# electrosteel2020_10_arrange6_synthboards.net
KiCad netlist of a schematic drawn in EAGLE
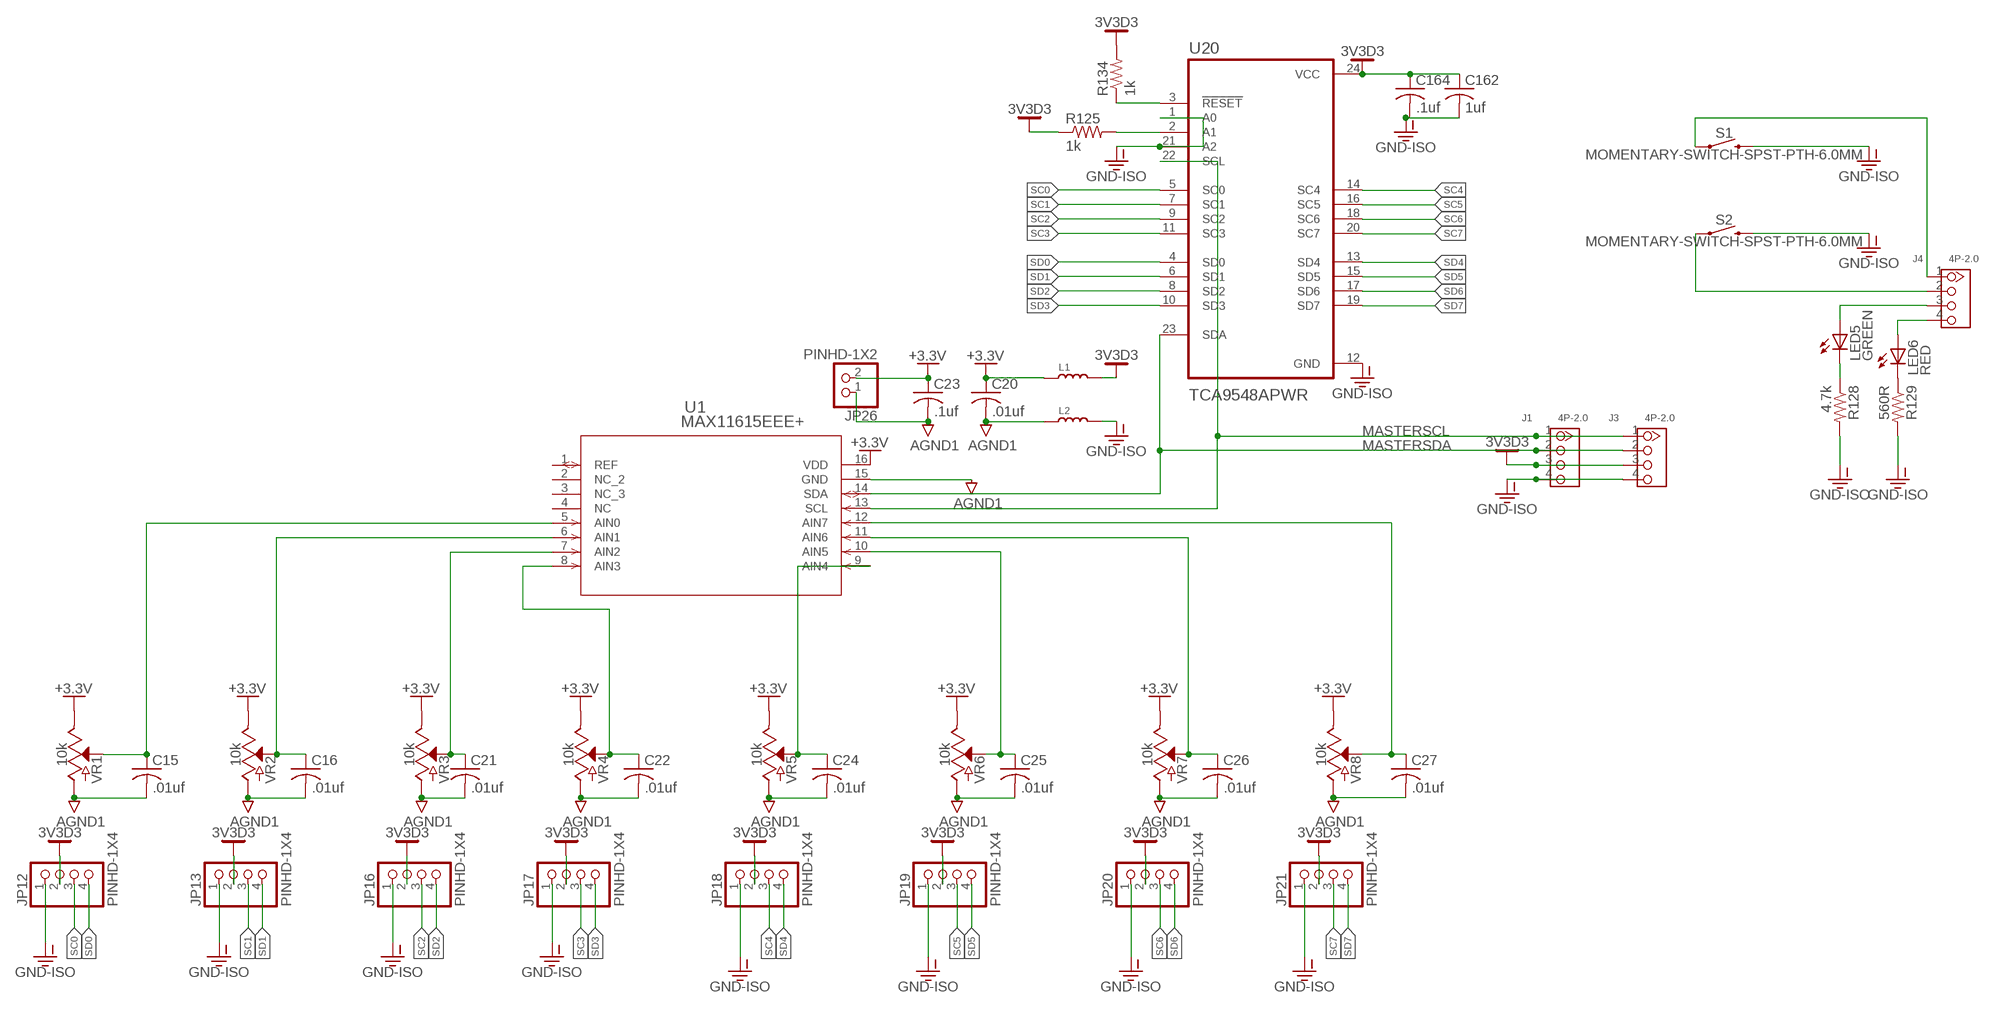
[diagram p0: schematic, sheet 1, part 1 of 2]
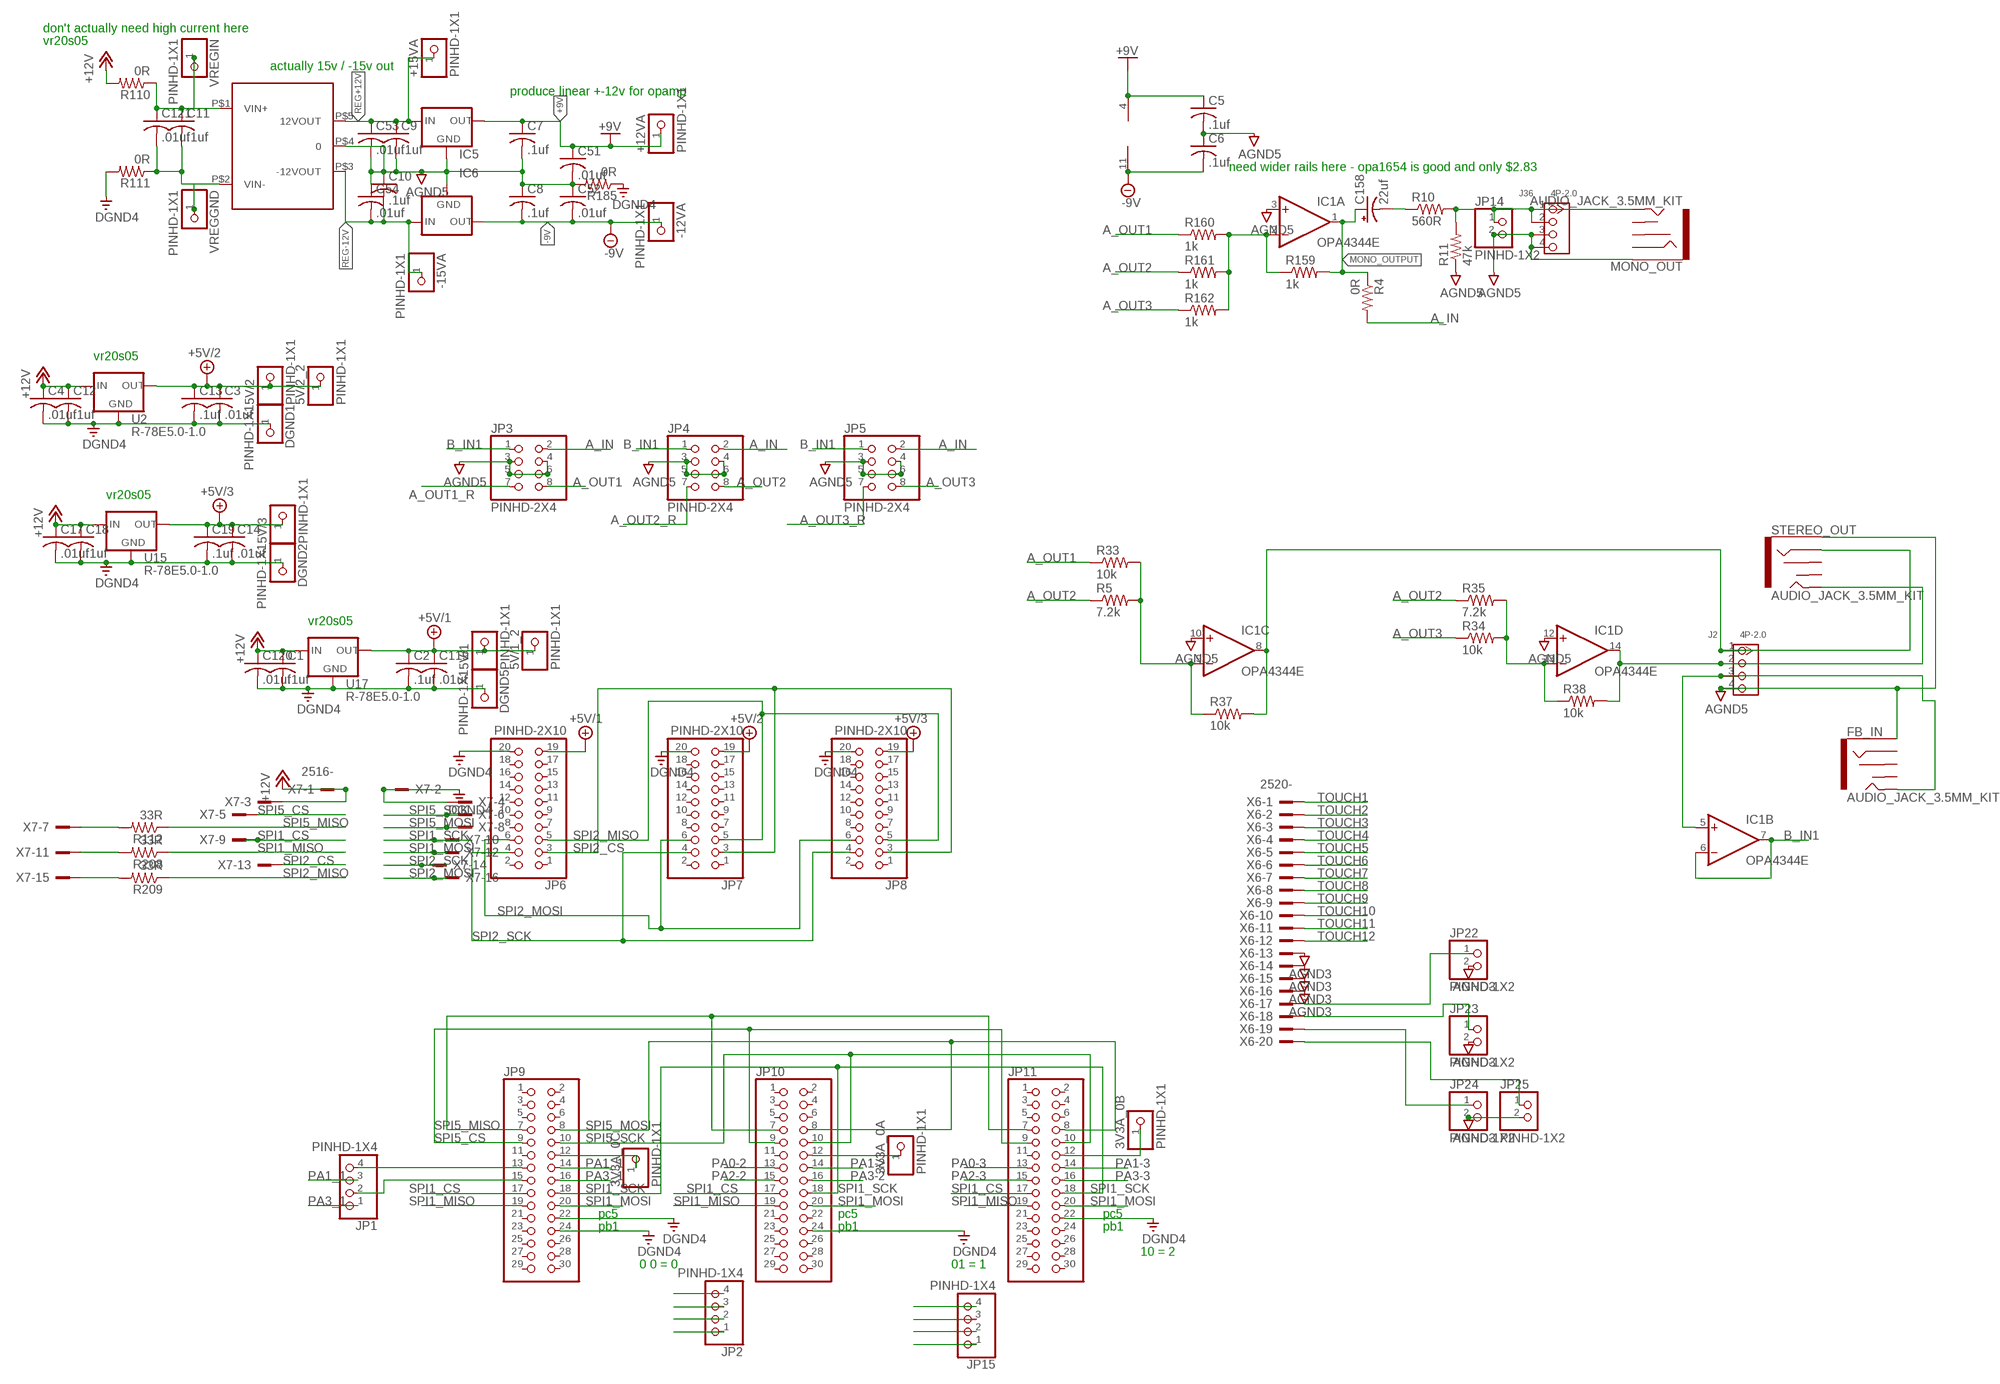
[diagram p1: schematic, sheet 1, part 2 of 2]

(export (version "E")
  (design (tool "Eeschema 10.0.6"))
  (components
    (comp (ref "+12VA")
      (value "PINHD-1X1")
      (footprint "eagle-import:1X01")
      (fields (field (name "PARTNO") "*DNP"))
      (libsource (lib "eagle-import") (part "PINHD-1X1"))
    )
    (comp (ref "+15VA")
      (value "PINHD-1X1")
      (footprint "eagle-import:1X01")
      (fields (field (name "PARTNO") "*DNP"))
      (libsource (lib "eagle-import") (part "PINHD-1X1"))
    )
    (comp (ref "-12VA")
      (value "PINHD-1X1")
      (footprint "eagle-import:1X01")
      (fields (field (name "PARTNO") "*DNP"))
      (libsource (lib "eagle-import") (part "PINHD-1X1"))
    )
    (comp (ref "-15VA")
      (value "PINHD-1X1")
      (footprint "eagle-import:1X01")
      (fields (field (name "PARTNO") "*DNP"))
      (libsource (lib "eagle-import") (part "PINHD-1X1"))
    )
    (comp (ref "3V3A_0A")
      (value "PINHD-1X1")
      (footprint "eagle-import:1X01")
      (fields (field (name "PARTNO") "*DNP"))
      (libsource (lib "eagle-import") (part "PINHD-1X1"))
    )
    (comp (ref "3V3A_0B")
      (value "PINHD-1X1")
      (footprint "eagle-import:1X01")
      (fields (field (name "PARTNO") "*DNP"))
      (libsource (lib "eagle-import") (part "PINHD-1X1"))
    )
    (comp (ref "3V3A_0C")
      (value "PINHD-1X1")
      (footprint "eagle-import:1X01")
      (fields (field (name "PARTNO") "*DNP"))
      (libsource (lib "eagle-import") (part "PINHD-1X1"))
    )
    (comp (ref "5V/1")
      (value "PINHD-1X1")
      (footprint "eagle-import:1X01")
      (fields (field (name "PARTNO") "*DNP"))
      (libsource (lib "eagle-import") (part "PINHD-1X1"))
    )
    (comp (ref "5V/1_2")
      (value "PINHD-1X1")
      (footprint "eagle-import:1X01")
      (fields (field (name "PARTNO") "*DNP"))
      (libsource (lib "eagle-import") (part "PINHD-1X1"))
    )
    (comp (ref "5V/2")
      (value "PINHD-1X1")
      (footprint "eagle-import:1X01")
      (fields (field (name "PARTNO") "*DNP"))
      (libsource (lib "eagle-import") (part "PINHD-1X1"))
    )
    (comp (ref "5V/2_2")
      (value "PINHD-1X1")
      (footprint "eagle-import:1X01")
      (fields (field (name "PARTNO") "*DNP"))
      (libsource (lib "eagle-import") (part "PINHD-1X1"))
    )
    (comp (ref "5V/3")
      (value "PINHD-1X1")
      (footprint "eagle-import:1X01")
      (fields (field (name "PARTNO") "*DNP"))
      (libsource (lib "eagle-import") (part "PINHD-1X1"))
    )
    (comp (ref "C1")
      (value ".1uf")
      (footprint "eagle-import:C0603")
      (fields (field (name "PARTNO") "TMK063B7103KP-F"))
      (libsource (lib "eagle-import") (part "rcl_334_C-USC0603"))
    )
    (comp (ref "C2")
      (value ".1uf")
      (footprint "eagle-import:C0603")
      (fields (field (name "PARTNO") "TMK063B7103KP-F"))
      (libsource (lib "eagle-import") (part "rcl_334_C-USC0603"))
    )
    (comp (ref "C3")
      (value ".01uf")
      (footprint "eagle-import:C0603")
      (fields (field (name "PARTNO") "TMK063B7103KP-F"))
      (libsource (lib "eagle-import") (part "rcl_334_C-USC0603"))
    )
    (comp (ref "C4")
      (value ".01uf")
      (footprint "eagle-import:C0603")
      (fields (field (name "PARTNO") "TMK063B7103KP-F"))
      (libsource (lib "eagle-import") (part "rcl_334_C-USC0603"))
    )
    (comp (ref "C5")
      (value ".1uf")
      (footprint "eagle-import:C0603")
      (fields (field (name "PARTNO") "TMK063B7103KP-F"))
      (libsource (lib "eagle-import") (part "rcl_334_C-USC0603"))
    )
    (comp (ref "C6")
      (value ".1uf")
      (footprint "eagle-import:C0603")
      (fields (field (name "PARTNO") "TMK063B7103KP-F"))
      (libsource (lib "eagle-import") (part "rcl_334_C-USC0603"))
    )
    (comp (ref "C7")
      (value ".1uf")
      (footprint "eagle-import:C0603")
      (fields (field (name "PARTNO") "TMK063B7103KP-F"))
      (libsource (lib "eagle-import") (part "rcl_334_C-USC0603"))
    )
    (comp (ref "C8")
      (value ".1uf")
      (footprint "eagle-import:C0603")
      (fields (field (name "PARTNO") "TMK063B7103KP-F"))
      (libsource (lib "eagle-import") (part "rcl_334_C-USC0603"))
    )
    (comp (ref "C9")
      (value ".1uf")
      (footprint "eagle-import:C0603")
      (fields (field (name "PARTNO") "TMK063B7103KP-F"))
      (libsource (lib "eagle-import") (part "rcl_334_C-USC0603"))
    )
    (comp (ref "C10")
      (value ".1uf")
      (footprint "eagle-import:C0603")
      (fields (field (name "PARTNO") "TMK063B7103KP-F"))
      (libsource (lib "eagle-import") (part "rcl_334_C-USC0603"))
    )
    (comp (ref "C11")
      (value ".1uf")
      (footprint "eagle-import:C0603")
      (fields (field (name "PARTNO") "TMK063B7103KP-F"))
      (libsource (lib "eagle-import") (part "rcl_334_C-USC0603"))
    )
    (comp (ref "C12")
      (value ".1uf")
      (footprint "eagle-import:C0603")
      (fields (field (name "PARTNO") "TMK063B7103KP-F"))
      (libsource (lib "eagle-import") (part "rcl_334_C-USC0603"))
    )
    (comp (ref "C13")
      (value ".1uf")
      (footprint "eagle-import:C0603")
      (fields (field (name "PARTNO") "TMK063B7103KP-F"))
      (libsource (lib "eagle-import") (part "rcl_334_C-USC0603"))
    )
    (comp (ref "C14")
      (value ".01uf")
      (footprint "eagle-import:C0603")
      (fields (field (name "PARTNO") "TMK063B7103KP-F"))
      (libsource (lib "eagle-import") (part "rcl_334_C-USC0603"))
    )
    (comp (ref "C15")
      (value ".01uf")
      (footprint "eagle-import:C0603")
      (fields (field (name "PARTNO") "TMK063B7103KP-F"))
      (libsource (lib "eagle-import") (part "rcl_334_C-USC0603"))
    )
    (comp (ref "C16")
      (value ".01uf")
      (footprint "eagle-import:C0603")
      (fields (field (name "PARTNO") "TMK063B7103KP-F"))
      (libsource (lib "eagle-import") (part "rcl_334_C-USC0603"))
    )
    (comp (ref "C17")
      (value ".01uf")
      (footprint "eagle-import:C0603")
      (fields (field (name "PARTNO") "TMK063B7103KP-F"))
      (libsource (lib "eagle-import") (part "rcl_334_C-USC0603"))
    )
    (comp (ref "C18")
      (value ".1uf")
      (footprint "eagle-import:C0603")
      (fields (field (name "PARTNO") "TMK063B7103KP-F"))
      (libsource (lib "eagle-import") (part "rcl_334_C-USC0603"))
    )
    (comp (ref "C19")
      (value ".1uf")
      (footprint "eagle-import:C0603")
      (fields (field (name "PARTNO") "TMK063B7103KP-F"))
      (libsource (lib "eagle-import") (part "rcl_334_C-USC0603"))
    )
    (comp (ref "C20")
      (value ".01uf")
      (footprint "eagle-import:C0603")
      (fields (field (name "PARTNO") "TMK063B7103KP-F"))
      (libsource (lib "eagle-import") (part "rcl_334_C-USC0603"))
    )
    (comp (ref "C21")
      (value ".01uf")
      (footprint "eagle-import:C0603")
      (fields (field (name "PARTNO") "TMK063B7103KP-F"))
      (libsource (lib "eagle-import") (part "rcl_334_C-USC0603"))
    )
    (comp (ref "C22")
      (value ".01uf")
      (footprint "eagle-import:C0603")
      (fields (field (name "PARTNO") "TMK063B7103KP-F"))
      (libsource (lib "eagle-import") (part "rcl_334_C-USC0603"))
    )
    (comp (ref "C23")
      (value ".1uf")
      (footprint "eagle-import:C0603")
      (fields (field (name "PARTNO") "TMK063B7103KP-F"))
      (libsource (lib "eagle-import") (part "rcl_334_C-USC0603"))
    )
    (comp (ref "C24")
      (value ".01uf")
      (footprint "eagle-import:C0603")
      (fields (field (name "PARTNO") "TMK063B7103KP-F"))
      (libsource (lib "eagle-import") (part "rcl_334_C-USC0603"))
    )
    (comp (ref "C25")
      (value ".01uf")
      (footprint "eagle-import:C0603")
      (fields (field (name "PARTNO") "TMK063B7103KP-F"))
      (libsource (lib "eagle-import") (part "rcl_334_C-USC0603"))
    )
    (comp (ref "C26")
      (value ".01uf")
      (footprint "eagle-import:C0603")
      (fields (field (name "PARTNO") "TMK063B7103KP-F"))
      (libsource (lib "eagle-import") (part "rcl_334_C-USC0603"))
    )
    (comp (ref "C27")
      (value ".01uf")
      (footprint "eagle-import:C0603")
      (fields (field (name "PARTNO") "TMK063B7103KP-F"))
      (libsource (lib "eagle-import") (part "rcl_334_C-USC0603"))
    )
    (comp (ref "C51")
      (value ".01uf")
      (footprint "eagle-import:C0603")
      (fields (field (name "PARTNO") "TMK063B7103KP-F"))
      (libsource (lib "eagle-import") (part "rcl_334_C-USC0603"))
    )
    (comp (ref "C52")
      (value ".01uf")
      (footprint "eagle-import:C0603")
      (fields (field (name "PARTNO") "TMK063B7103KP-F"))
      (libsource (lib "eagle-import") (part "rcl_334_C-USC0603"))
    )
    (comp (ref "C53")
      (value ".01uf")
      (footprint "eagle-import:C0603")
      (fields (field (name "PARTNO") "TMK063B7103KP-F"))
      (libsource (lib "eagle-import") (part "rcl_334_C-USC0603"))
    )
    (comp (ref "C54")
      (value ".01uf")
      (footprint "eagle-import:C0603")
      (fields (field (name "PARTNO") "TMK063B7103KP-F"))
      (libsource (lib "eagle-import") (part "rcl_334_C-USC0603"))
    )
    (comp (ref "C119")
      (value ".01uf")
      (footprint "eagle-import:C0603")
      (fields (field (name "PARTNO") "TMK063B7103KP-F"))
      (libsource (lib "eagle-import") (part "rcl_334_C-USC0603"))
    )
    (comp (ref "C120")
      (value ".01uf")
      (footprint "eagle-import:C0603")
      (fields (field (name "PARTNO") "TMK063B7103KP-F"))
      (libsource (lib "eagle-import") (part "rcl_334_C-USC0603"))
    )
    (comp (ref "C121")
      (value ".01uf")
      (footprint "eagle-import:C0603")
      (fields (field (name "PARTNO") "TMK063B7103KP-F"))
      (libsource (lib "eagle-import") (part "rcl_334_C-USC0603"))
    )
    (comp (ref "C158")
      (value "22uf")
      (footprint "eagle-import:PANASONIC_D")
      (fields (field (name "PARTNO") "EEE-1CA220NP"))
      (libsource (lib "eagle-import") (part "CPOL-USD"))
    )
    (comp (ref "C162")
      (value "1uf")
      (footprint "eagle-import:C1206K")
      (fields (field (name "PARTNO") "C3216X7R1E105K085AA"))
      (libsource (lib "eagle-import") (part "C-USC1206K"))
    )
    (comp (ref "C164")
      (value ".1uf")
      (footprint "eagle-import:C0603K")
      (fields (field (name "PARTNO") "CC0603KRX7R8BB104"))
      (libsource (lib "eagle-import") (part "C-USC0603K"))
    )
    (comp (ref "DGND1")
      (value "PINHD-1X1")
      (footprint "eagle-import:1X01")
      (fields (field (name "PARTNO") "*DNP"))
      (libsource (lib "eagle-import") (part "PINHD-1X1"))
    )
    (comp (ref "DGND2")
      (value "PINHD-1X1")
      (footprint "eagle-import:1X01")
      (fields (field (name "PARTNO") "*DNP"))
      (libsource (lib "eagle-import") (part "PINHD-1X1"))
    )
    (comp (ref "DGND5")
      (value "PINHD-1X1")
      (footprint "eagle-import:1X01")
      (fields (field (name "PARTNO") "*DNP"))
      (libsource (lib "eagle-import") (part "PINHD-1X1"))
    )
    (comp (ref "FB_IN")
      (value "AUDIO_JACK_3.5MM_KIT")
      (footprint "eagle-import:AUDIO-JACK-KIT")
      (libsource (lib "eagle-import") (part "AUDIO_JACK_3.5MM_KIT"))
    )
    (comp (ref "IC1")
      (value "OPA4344E")
      (footprint "eagle-import:TSSOP14")
      (fields (field (name "PARTNO") "OPA1654AIPWR"))
      (libsource (lib "eagle-import") (part "OPA4E344"))
    )
    (comp (ref "IC5")
      (value "78LXX")
      (footprint "eagle-import:78LXX")
      (fields (field (name "PARTNO") "LM78L12ACZ/LFT7"))
      (libsource (lib "eagle-import") (part "78LXX"))
    )
    (comp (ref "IC6")
      (value "79LXX")
      (footprint "eagle-import:79LXX")
      (fields (field (name "PARTNO") "L79L12ACZ-TR"))
      (libsource (lib "eagle-import") (part "79LXX"))
    )
    (comp (ref "J1")
      (value "4P-2.0")
      (footprint "eagle-import:HW4-2.0")
      (fields (field (name "PARTNO") "110990030"))
      (libsource (lib "eagle-import") (part "GROVE-CONNECTOR-DIP(4P-2.0)"))
    )
    (comp (ref "J2")
      (value "4P-2.0")
      (footprint "eagle-import:HW4-2.0")
      (fields (field (name "PARTNO") "110990030"))
      (libsource (lib "eagle-import") (part "GROVE-CONNECTOR-DIP(4P-2.0)"))
    )
    (comp (ref "J3")
      (value "4P-2.0")
      (footprint "eagle-import:HW4-2.0")
      (fields (field (name "PARTNO") "110990030"))
      (libsource (lib "eagle-import") (part "GROVE-CONNECTOR-DIP(4P-2.0)"))
    )
    (comp (ref "J4")
      (value "4P-2.0")
      (footprint "eagle-import:HW4-2.0")
      (fields (field (name "PARTNO") "110990030"))
      (libsource (lib "eagle-import") (part "GROVE-CONNECTOR-DIP(4P-2.0)"))
    )
    (comp (ref "J36")
      (value "4P-2.0")
      (footprint "eagle-import:HW4-2.0")
      (fields (field (name "PARTNO") "110990030"))
      (libsource (lib "eagle-import") (part "GROVE-CONNECTOR-DIP(4P-2.0)"))
    )
    (comp (ref "JP1")
      (value "PINHD-1X4")
      (footprint "eagle-import:1X04")
      (libsource (lib "eagle-import") (part "PINHD-1X4"))
    )
    (comp (ref "JP2")
      (value "PINHD-1X4")
      (footprint "eagle-import:1X04")
      (libsource (lib "eagle-import") (part "PINHD-1X4"))
    )
    (comp (ref "JP3")
      (value "PINHD-2X4")
      (footprint "eagle-import:2X04")
      (fields (field (name "PARTNO") "77313-101-08LF"))
      (libsource (lib "eagle-import") (part "PINHD-2X4"))
    )
    (comp (ref "JP4")
      (value "PINHD-2X4")
      (footprint "eagle-import:2X04")
      (fields (field (name "PARTNO") "77313-101-08LF"))
      (libsource (lib "eagle-import") (part "PINHD-2X4"))
    )
    (comp (ref "JP5")
      (value "PINHD-2X4")
      (footprint "eagle-import:2X04")
      (fields (field (name "PARTNO") "77313-101-08LF"))
      (libsource (lib "eagle-import") (part "PINHD-2X4"))
    )
    (comp (ref "JP6")
      (value "PINHD-2X10")
      (footprint "eagle-import:2X10")
      (fields (field (name "PARTNO") "77313-101-20LF"))
      (libsource (lib "eagle-import") (part "PINHD-2X10"))
    )
    (comp (ref "JP7")
      (value "PINHD-2X10")
      (footprint "eagle-import:2X10")
      (fields (field (name "PARTNO") "77313-101-20LF"))
      (libsource (lib "eagle-import") (part "PINHD-2X10"))
    )
    (comp (ref "JP8")
      (value "PINHD-2X10")
      (footprint "eagle-import:2X10")
      (fields (field (name "PARTNO") "77313-101-20LF"))
      (libsource (lib "eagle-import") (part "PINHD-2X10"))
    )
    (comp (ref "JP9")
      (value "PINHD-2X15")
      (footprint "eagle-import:2X15")
      (fields (field (name "PARTNO") "77313-101-30LF"))
      (libsource (lib "eagle-import") (part "PINHD-2X15"))
    )
    (comp (ref "JP10")
      (value "PINHD-2X15")
      (footprint "eagle-import:2X15")
      (fields (field (name "PARTNO") "77313-101-30LF"))
      (libsource (lib "eagle-import") (part "PINHD-2X15"))
    )
    (comp (ref "JP11")
      (value "PINHD-2X15")
      (footprint "eagle-import:2X15")
      (fields (field (name "PARTNO") "77313-101-30LF"))
      (libsource (lib "eagle-import") (part "PINHD-2X15"))
    )
    (comp (ref "JP12")
      (value "PINHD-1X4")
      (footprint "eagle-import:1X04")
      (libsource (lib "eagle-import") (part "PINHD-1X4"))
    )
    (comp (ref "JP13")
      (value "PINHD-1X4")
      (footprint "eagle-import:1X04")
      (libsource (lib "eagle-import") (part "PINHD-1X4"))
    )
    (comp (ref "JP14")
      (value "PINHD-1X2")
      (footprint "eagle-import:1X02")
      (fields (field (name "PARTNO") "*DNP"))
      (libsource (lib "eagle-import") (part "PINHD-1X2"))
    )
    (comp (ref "JP15")
      (value "PINHD-1X4")
      (footprint "eagle-import:1X04")
      (libsource (lib "eagle-import") (part "PINHD-1X4"))
    )
    (comp (ref "JP16")
      (value "PINHD-1X4")
      (footprint "eagle-import:1X04")
      (libsource (lib "eagle-import") (part "PINHD-1X4"))
    )
    (comp (ref "JP17")
      (value "PINHD-1X4")
      (footprint "eagle-import:1X04")
      (libsource (lib "eagle-import") (part "PINHD-1X4"))
    )
    (comp (ref "JP18")
      (value "PINHD-1X4")
      (footprint "eagle-import:1X04")
      (libsource (lib "eagle-import") (part "PINHD-1X4"))
    )
    (comp (ref "JP19")
      (value "PINHD-1X4")
      (footprint "eagle-import:1X04")
      (libsource (lib "eagle-import") (part "PINHD-1X4"))
    )
    (comp (ref "JP20")
      (value "PINHD-1X4")
      (footprint "eagle-import:1X04")
      (libsource (lib "eagle-import") (part "PINHD-1X4"))
    )
    (comp (ref "JP21")
      (value "PINHD-1X4")
      (footprint "eagle-import:1X04")
      (libsource (lib "eagle-import") (part "PINHD-1X4"))
    )
    (comp (ref "JP22")
      (value "PINHD-1X2")
      (footprint "eagle-import:1X02")
      (fields (field (name "PARTNO") "*DNP"))
      (libsource (lib "eagle-import") (part "PINHD-1X2"))
    )
    (comp (ref "JP23")
      (value "PINHD-1X2")
      (footprint "eagle-import:1X02")
      (fields (field (name "PARTNO") "*DNP"))
      (libsource (lib "eagle-import") (part "PINHD-1X2"))
    )
    (comp (ref "JP24")
      (value "PINHD-1X2")
      (footprint "eagle-import:1X02")
      (fields (field (name "PARTNO") "*DNP"))
      (libsource (lib "eagle-import") (part "PINHD-1X2"))
    )
    (comp (ref "JP25")
      (value "PINHD-1X2")
      (footprint "eagle-import:1X02")
      (fields (field (name "PARTNO") "*DNP"))
      (libsource (lib "eagle-import") (part "PINHD-1X2"))
    )
    (comp (ref "JP26")
      (value "PINHD-1X2")
      (footprint "eagle-import:1X02")
      (libsource (lib "eagle-import") (part "PINHD-1X2"))
    )
    (comp (ref "L1")
      (value "INDUCTOR/FERRITE-BEAD0603")
      (footprint "eagle-import:INDUCTOR_L0603")
      (libsource (lib "eagle-import") (part "INDUCTOR/FERRITE-BEAD0603"))
    )
    (comp (ref "L2")
      (value "INDUCTOR/FERRITE-BEAD0603")
      (footprint "eagle-import:INDUCTOR_L0603")
      (libsource (lib "eagle-import") (part "INDUCTOR/FERRITE-BEAD0603"))
    )
    (comp (ref "LED5")
      (value "GREEN")
      (footprint "eagle-import:P-LCC-2")
      (fields (field (name "PARTNO") "HSMM-A101-R00J1"))
      (libsource (lib "eagle-import") (part "LEDP-LCC-2"))
    )
    (comp (ref "LED6")
      (value "RED")
      (footprint "eagle-import:P-LCC-2")
      (fields (field (name "PARTNO") "HSMZ-A100-R00J1"))
      (libsource (lib "eagle-import") (part "LEDP-LCC-2"))
    )
    (comp (ref "MONO_OUT")
      (value "AUDIO_JACK_3.5MM_KIT")
      (footprint "eagle-import:AUDIO-JACK-KIT")
      (libsource (lib "eagle-import") (part "AUDIO_JACK_3.5MM_KIT"))
    )
    (comp (ref "R4")
      (value "0R")
      (footprint "eagle-import:R0603")
      (fields (field (name "PARTNO") "RCS06030000Z0EA"))
      (libsource (lib "eagle-import") (part "R-US_R0603"))
    )
    (comp (ref "R5")
      (value "7.2k")
      (footprint "eagle-import:R0603")
      (fields (field (name "PARTNO") "ESR03EZPF1001"))
      (libsource (lib "eagle-import") (part "R-US_R0603"))
    )
    (comp (ref "R10")
      (value "560R")
      (footprint "eagle-import:R0603")
      (fields (field (name "PARTNO") "ESR03EZPF5600"))
      (libsource (lib "eagle-import") (part "R-US_R0603"))
    )
    (comp (ref "R11")
      (value "47k")
      (footprint "eagle-import:R0603")
      (fields (field (name "PARTNO") "ESR03EZPJ473"))
      (libsource (lib "eagle-import") (part "R-US_R0603"))
    )
    (comp (ref "R33")
      (value "10k")
      (footprint "eagle-import:R0603")
      (fields (field (name "PARTNO") "ESR03EZPF1001"))
      (libsource (lib "eagle-import") (part "R-US_R0603"))
    )
    (comp (ref "R34")
      (value "10k")
      (footprint "eagle-import:R0603")
      (fields (field (name "PARTNO") "ESR03EZPF1001"))
      (libsource (lib "eagle-import") (part "R-US_R0603"))
    )
    (comp (ref "R35")
      (value "7.2k")
      (footprint "eagle-import:R0603")
      (fields (field (name "PARTNO") "ESR03EZPF1001"))
      (libsource (lib "eagle-import") (part "R-US_R0603"))
    )
    (comp (ref "R37")
      (value "10k")
      (footprint "eagle-import:R0603")
      (fields (field (name "PARTNO") "ESR03EZPF1001"))
      (libsource (lib "eagle-import") (part "R-US_R0603"))
    )
    (comp (ref "R38")
      (value "10k")
      (footprint "eagle-import:R0603")
      (fields (field (name "PARTNO") "ESR03EZPF1001"))
      (libsource (lib "eagle-import") (part "R-US_R0603"))
    )
    (comp (ref "R110")
      (value "0R")
      (footprint "eagle-import:R0603")
      (fields (field (name "PARTNO") "RCS06030000Z0EA"))
      (libsource (lib "eagle-import") (part "R-US_R0603"))
    )
    (comp (ref "R111")
      (value "0R")
      (footprint "eagle-import:R0603")
      (fields (field (name "PARTNO") "RCS06030000Z0EA"))
      (libsource (lib "eagle-import") (part "R-US_R0603"))
    )
    (comp (ref "R112")
      (value "33R")
      (footprint "eagle-import:R0603")
      (fields (field (name "PARTNO") "RC0201FR-0733RL"))
      (libsource (lib "eagle-import") (part "rcl_334_R-US_R0603"))
    )
    (comp (ref "R125")
      (value "1k")
      (footprint "eagle-import:R0603")
      (fields (field (name "PARTNO") "ESR03EZPF1001"))
      (libsource (lib "eagle-import") (part "R-US_R0603"))
    )
    (comp (ref "R128")
      (value "4.7k")
      (footprint "eagle-import:R0603")
      (fields (field (name "PARTNO") "ESR03EZPF5600"))
      (libsource (lib "eagle-import") (part "R-US_R0603"))
    )
    (comp (ref "R129")
      (value "560R")
      (footprint "eagle-import:R0603")
      (fields (field (name "PARTNO") "ESR03EZPF5600"))
      (libsource (lib "eagle-import") (part "R-US_R0603"))
    )
    (comp (ref "R134")
      (value "1k")
      (footprint "eagle-import:R0603")
      (fields (field (name "PARTNO") "ESR03EZPF1001"))
      (libsource (lib "eagle-import") (part "R-US_R0603"))
    )
    (comp (ref "R159")
      (value "1k")
      (footprint "eagle-import:R0603")
      (fields (field (name "PARTNO") "ESR03EZPF1001"))
      (libsource (lib "eagle-import") (part "R-US_R0603"))
    )
    (comp (ref "R160")
      (value "1k")
      (footprint "eagle-import:R0603")
      (fields (field (name "PARTNO") "ESR03EZPF1001"))
      (libsource (lib "eagle-import") (part "R-US_R0603"))
    )
    (comp (ref "R161")
      (value "1k")
      (footprint "eagle-import:R0603")
      (fields (field (name "PARTNO") "ESR03EZPF1001"))
      (libsource (lib "eagle-import") (part "R-US_R0603"))
    )
    (comp (ref "R162")
      (value "1k")
      (footprint "eagle-import:R0603")
      (fields (field (name "PARTNO") "ESR03EZPF1001"))
      (libsource (lib "eagle-import") (part "R-US_R0603"))
    )
    (comp (ref "R185")
      (value "0R")
      (footprint "eagle-import:R0603")
      (fields (field (name "PARTNO") "RCS06030000Z0EA"))
      (libsource (lib "eagle-import") (part "R-US_R0603"))
    )
    (comp (ref "R208")
      (value "33R")
      (footprint "eagle-import:R0603")
      (fields (field (name "PARTNO") "RC0201FR-0733RL"))
      (libsource (lib "eagle-import") (part "rcl_334_R-US_R0603"))
    )
    (comp (ref "R209")
      (value "33R")
      (footprint "eagle-import:R0603")
      (fields (field (name "PARTNO") "RC0201FR-0733RL"))
      (libsource (lib "eagle-import") (part "rcl_334_R-US_R0603"))
    )
    (comp (ref "S1")
      (value "MOMENTARY-SWITCH-SPST-PTH-6.0MM")
      (footprint "eagle-import:TACTILE_SWITCH_PTH_6.0MM")
      (fields (field (name "PARTNO") "TL1105SPF160Q"))
      (libsource (lib "eagle-import") (part "MOMENTARY-SWITCH-SPST-PTH-6.0MM"))
    )
    (comp (ref "S2")
      (value "MOMENTARY-SWITCH-SPST-PTH-6.0MM")
      (footprint "eagle-import:TACTILE_SWITCH_PTH_6.0MM")
      (fields (field (name "PARTNO") "TL1105SPF160Q"))
      (libsource (lib "eagle-import") (part "MOMENTARY-SWITCH-SPST-PTH-6.0MM"))
    )
    (comp (ref "STEREO_OUT")
      (value "AUDIO_JACK_3.5MM_KIT")
      (footprint "eagle-import:AUDIO-JACK-KIT")
      (libsource (lib "eagle-import") (part "AUDIO_JACK_3.5MM_KIT"))
    )
    (comp (ref "U$3")
      (value "CMR0512S3C")
      (footprint "eagle-import:CMR0512S3C")
      (fields (field (name "PARTNO") "DPU01M-15"))
      (libsource (lib "eagle-import") (part "CMR0512S3C"))
    )
    (comp (ref "U1")
      (value "MAX11615EEE+")
      (footprint "eagle-import:21-0055H_16_MXM")
      (fields (field (name "MANUFACTURER_PART_NUMBER") "max11615eee+"))
      (libsource (lib "eagle-import") (part "MAX11615EEE+"))
    )
    (comp (ref "U2")
      (value "R-78E5.0-1.0")
      (footprint "eagle-import:DC-DC_CONVERTER_78XX")
      (libsource (lib "eagle-import") (part "R-78E5.0-1.0"))
    )
    (comp (ref "U15")
      (value "R-78E5.0-1.0")
      (footprint "eagle-import:DC-DC_CONVERTER_78XX")
      (libsource (lib "eagle-import") (part "R-78E5.0-1.0"))
    )
    (comp (ref "U17")
      (value "R-78E5.0-1.0")
      (footprint "eagle-import:DC-DC_CONVERTER_78XX")
      (libsource (lib "eagle-import") (part "R-78E5.0-1.0"))
    )
    (comp (ref "U20")
      (value "TCA9548APWR")
      (footprint "eagle-import:SOP65P640X120-24N")
      (fields (field (name "MF") "Texas Instruments"))
      (libsource (lib "eagle-import") (part "TCA9548APWR"))
    )
    (comp (ref "VR1")
      (value "10k")
      (footprint "eagle-import:POT-PTH-ALPS")
      (libsource (lib "eagle-import") (part "POTENTIOMETER-PTH-9MM-1/20W-20%"))
    )
    (comp (ref "VR2")
      (value "10k")
      (footprint "eagle-import:POT-PTH-ALPS")
      (libsource (lib "eagle-import") (part "POTENTIOMETER-PTH-9MM-1/20W-20%"))
    )
    (comp (ref "VR3")
      (value "10k")
      (footprint "eagle-import:POT-PTH-ALPS")
      (libsource (lib "eagle-import") (part "POTENTIOMETER-PTH-9MM-1/20W-20%"))
    )
    (comp (ref "VR4")
      (value "10k")
      (footprint "eagle-import:POT-PTH-ALPS")
      (libsource (lib "eagle-import") (part "POTENTIOMETER-PTH-9MM-1/20W-20%"))
    )
    (comp (ref "VR5")
      (value "10k")
      (footprint "eagle-import:POT-PTH-ALPS")
      (libsource (lib "eagle-import") (part "POTENTIOMETER-PTH-9MM-1/20W-20%"))
    )
    (comp (ref "VR6")
      (value "10k")
      (footprint "eagle-import:POT-PTH-ALPS")
      (libsource (lib "eagle-import") (part "POTENTIOMETER-PTH-9MM-1/20W-20%"))
    )
    (comp (ref "VR7")
      (value "10k")
      (footprint "eagle-import:POT-PTH-ALPS")
      (libsource (lib "eagle-import") (part "POTENTIOMETER-PTH-9MM-1/20W-20%"))
    )
    (comp (ref "VR8")
      (value "10k")
      (footprint "eagle-import:POT-PTH-ALPS")
      (libsource (lib "eagle-import") (part "POTENTIOMETER-PTH-9MM-1/20W-20%"))
    )
    (comp (ref "VREGGND")
      (value "PINHD-1X1")
      (footprint "eagle-import:1X01")
      (fields (field (name "PARTNO") "*DNP"))
      (libsource (lib "eagle-import") (part "PINHD-1X1"))
    )
    (comp (ref "VREGIN")
      (value "PINHD-1X1")
      (footprint "eagle-import:1X01")
      (fields (field (name "PARTNO") "*DNP"))
      (libsource (lib "eagle-import") (part "PINHD-1X1"))
    )
    (comp (ref "X6")
      (value "2520-")
      (footprint "eagle-import:PAK100_2500-20")
      (fields (field (name "PARTNO") "N2520-6003-UG"))
      (libsource (lib "eagle-import") (part "2520-"))
    )
    (comp (ref "X7")
      (value "2516-")
      (footprint "eagle-import:PAK100_2500-16")
      (fields (field (name "PARTNO") "D2516-6002-AR"))
      (libsource (lib "eagle-import") (part "2516-"))
    )
  )
  (nets
    (net (code "1") (name "+3.3V") (class "Default")
      (node (ref "C20") (pin "1") (pinfunction "1_1") (pintype "passive"))
      (node (ref "C23") (pin "1") (pinfunction "1_1") (pintype "passive"))
      (node (ref "JP26") (pin "2") (pinfunction "2_2") (pintype "passive"))
      (node (ref "L1") (pin "1") (pinfunction "1_1") (pintype "passive"))
      (node (ref "U1") (pin "16") (pinfunction "VDD_16") (pintype "power_in"))
      (node (ref "VR1") (pin "P$1") (pinfunction "E_P$1") (pintype "passive"))
      (node (ref "VR2") (pin "P$1") (pinfunction "E_P$1") (pintype "passive"))
      (node (ref "VR3") (pin "P$1") (pinfunction "E_P$1") (pintype "passive"))
      (node (ref "VR4") (pin "P$1") (pinfunction "E_P$1") (pintype "passive"))
      (node (ref "VR5") (pin "P$1") (pinfunction "E_P$1") (pintype "passive"))
      (node (ref "VR6") (pin "P$1") (pinfunction "E_P$1") (pintype "passive"))
      (node (ref "VR7") (pin "P$1") (pinfunction "E_P$1") (pintype "passive"))
      (node (ref "VR8") (pin "P$1") (pinfunction "E_P$1") (pintype "passive"))
    )
    (net (code "2") (name "+5V{slash}1") (class "Default")
      (node (ref "5V/1") (pin "1") (pinfunction "1_1") (pintype "passive"))
      (node (ref "5V/1_2") (pin "1") (pinfunction "1_1") (pintype "passive"))
      (node (ref "C119") (pin "1") (pinfunction "1_1") (pintype "passive"))
      (node (ref "C2") (pin "1") (pinfunction "1_1") (pintype "passive"))
      (node (ref "JP6") (pin "19") (pinfunction "19_19") (pintype "passive"))
      (node (ref "U17") (pin "VOUT") (pinfunction "OUT_VOUT") (pintype "passive"))
    )
    (net (code "3") (name "+5V{slash}2") (class "Default")
      (node (ref "5V/2") (pin "1") (pinfunction "1_1") (pintype "passive"))
      (node (ref "5V/2_2") (pin "1") (pinfunction "1_1") (pintype "passive"))
      (node (ref "C13") (pin "1") (pinfunction "1_1") (pintype "passive"))
      (node (ref "C3") (pin "1") (pinfunction "1_1") (pintype "passive"))
      (node (ref "JP7") (pin "19") (pinfunction "19_19") (pintype "passive"))
      (node (ref "U2") (pin "VOUT") (pinfunction "OUT_VOUT") (pintype "passive"))
    )
    (net (code "4") (name "+5V{slash}3") (class "Default")
      (node (ref "5V/3") (pin "1") (pinfunction "1_1") (pintype "passive"))
      (node (ref "C14") (pin "1") (pinfunction "1_1") (pintype "passive"))
      (node (ref "C19") (pin "1") (pinfunction "1_1") (pintype "passive"))
      (node (ref "JP8") (pin "19") (pinfunction "19_19") (pintype "passive"))
      (node (ref "U15") (pin "VOUT") (pinfunction "OUT_VOUT") (pintype "passive"))
    )
    (net (code "5") (name "+9V") (class "Default")
      (node (ref "+12VA") (pin "1") (pinfunction "1_1") (pintype "passive"))
      (node (ref "C5") (pin "1") (pinfunction "1_1") (pintype "passive"))
      (node (ref "C51") (pin "1") (pinfunction "1_1") (pintype "passive"))
      (node (ref "C7") (pin "1") (pinfunction "1_1") (pintype "passive"))
      (node (ref "IC1") (pin "4") (pinfunction "V+_4") (pintype "power_in"))
      (node (ref "IC5") (pin "OUT") (pinfunction "OUT_OUT") (pintype "passive"))
    )
    (net (code "6") (name "+12V") (class "Default")
      (node (ref "C1") (pin "1") (pinfunction "1_1") (pintype "passive"))
      (node (ref "C12") (pin "1") (pinfunction "1_1") (pintype "passive"))
      (node (ref "C120") (pin "1") (pinfunction "1_1") (pintype "passive"))
      (node (ref "C17") (pin "1") (pinfunction "1_1") (pintype "passive"))
      (node (ref "C18") (pin "1") (pinfunction "1_1") (pintype "passive"))
      (node (ref "C4") (pin "1") (pinfunction "1_1") (pintype "passive"))
      (node (ref "R110") (pin "2") (pinfunction "2_2") (pintype "passive"))
      (node (ref "U15") (pin "VIN") (pinfunction "IN_VIN") (pintype "input"))
      (node (ref "U17") (pin "VIN") (pinfunction "IN_VIN") (pintype "input"))
      (node (ref "U2") (pin "VIN") (pinfunction "IN_VIN") (pintype "input"))
      (node (ref "X7") (pin "1") (pinfunction "KL_1") (pintype "passive"))
      (node (ref "X7") (pin "3") (pinfunction "KL_3") (pintype "passive"))
    )
    (net (code "7") (name "-9V") (class "Default")
      (node (ref "-12VA") (pin "1") (pinfunction "1_1") (pintype "passive"))
      (node (ref "C52") (pin "2") (pinfunction "2_2") (pintype "passive"))
      (node (ref "C6") (pin "2") (pinfunction "2_2") (pintype "passive"))
      (node (ref "C8") (pin "2") (pinfunction "2_2") (pintype "passive"))
      (node (ref "IC1") (pin "11") (pinfunction "V-_11") (pintype "power_in"))
      (node (ref "IC6") (pin "OUT") (pinfunction "OUT_OUT") (pintype "passive"))
    )
    (net (code "8") (name "/A_IN") (class "Default")
      (node (ref "JP3") (pin "2") (pinfunction "2_2") (pintype "passive"))
      (node (ref "JP4") (pin "2") (pinfunction "2_2") (pintype "passive"))
      (node (ref "JP5") (pin "2") (pinfunction "2_2") (pintype "passive"))
      (node (ref "R4") (pin "2") (pinfunction "2_2") (pintype "passive"))
    )
    (net (code "9") (name "/A_OUT1") (class "Default")
      (node (ref "JP3") (pin "8") (pinfunction "8_8") (pintype "passive"))
      (node (ref "R160") (pin "1") (pinfunction "1_1") (pintype "passive"))
      (node (ref "R33") (pin "1") (pinfunction "1_1") (pintype "passive"))
    )
    (net (code "10") (name "/A_OUT1_R") (class "Default")
      (node (ref "JP3") (pin "7") (pinfunction "7_7") (pintype "passive"))
    )
    (net (code "11") (name "/A_OUT2") (class "Default")
      (node (ref "JP4") (pin "8") (pinfunction "8_8") (pintype "passive"))
      (node (ref "R161") (pin "1") (pinfunction "1_1") (pintype "passive"))
      (node (ref "R35") (pin "1") (pinfunction "1_1") (pintype "passive"))
      (node (ref "R5") (pin "1") (pinfunction "1_1") (pintype "passive"))
    )
    (net (code "12") (name "/A_OUT2_R") (class "Default")
      (node (ref "JP4") (pin "7") (pinfunction "7_7") (pintype "passive"))
    )
    (net (code "13") (name "/A_OUT3") (class "Default")
      (node (ref "JP5") (pin "8") (pinfunction "8_8") (pintype "passive"))
      (node (ref "R162") (pin "1") (pinfunction "1_1") (pintype "passive"))
      (node (ref "R34") (pin "1") (pinfunction "1_1") (pintype "passive"))
    )
    (net (code "14") (name "/A_OUT3_R") (class "Default")
      (node (ref "JP5") (pin "7") (pinfunction "7_7") (pintype "passive"))
    )
    (net (code "15") (name "/B_IN1") (class "Default")
      (node (ref "IC1") (pin "6") (pinfunction "-IN_6") (pintype "input"))
      (node (ref "IC1") (pin "7") (pinfunction "OUT_7") (pintype "output"))
      (node (ref "JP3") (pin "1") (pinfunction "1_1") (pintype "passive"))
      (node (ref "JP4") (pin "1") (pinfunction "1_1") (pintype "passive"))
      (node (ref "JP5") (pin "1") (pinfunction "1_1") (pintype "passive"))
    )
    (net (code "16") (name "/MASTERSCL") (class "Default")
      (node (ref "J1") (pin "1") (pinfunction "1_1") (pintype "bidirectional"))
      (node (ref "J3") (pin "1") (pinfunction "1_1") (pintype "bidirectional"))
      (node (ref "U1") (pin "13") (pinfunction "SCL_13") (pintype "input"))
      (node (ref "U20") (pin "22") (pinfunction "SCL_22") (pintype "input"))
    )
    (net (code "17") (name "/MASTERSDA") (class "Default")
      (node (ref "J1") (pin "2") (pinfunction "2_2") (pintype "bidirectional"))
      (node (ref "J3") (pin "2") (pinfunction "2_2") (pintype "bidirectional"))
      (node (ref "U1") (pin "14") (pinfunction "SDA_14") (pintype "bidirectional"))
      (node (ref "U20") (pin "23") (pinfunction "SDA_23") (pintype "bidirectional"))
    )
    (net (code "18") (name "/PA0-2") (class "Default")
      (node (ref "JP10") (pin "13") (pinfunction "13_13") (pintype "passive"))
      (node (ref "JP2") (pin "4") (pinfunction "4_4") (pintype "passive"))
    )
    (net (code "19") (name "/PA0-3") (class "Default")
      (node (ref "JP11") (pin "13") (pinfunction "13_13") (pintype "passive"))
      (node (ref "JP15") (pin "4") (pinfunction "4_4") (pintype "passive"))
    )
    (net (code "20") (name "/PA1-2") (class "Default")
      (node (ref "JP10") (pin "14") (pinfunction "14_14") (pintype "passive"))
      (node (ref "JP2") (pin "3") (pinfunction "3_3") (pintype "passive"))
    )
    (net (code "21") (name "/PA1-3") (class "Default")
      (node (ref "JP11") (pin "14") (pinfunction "14_14") (pintype "passive"))
      (node (ref "JP15") (pin "3") (pinfunction "3_3") (pintype "passive"))
    )
    (net (code "22") (name "/PA1_1") (class "Default")
      (node (ref "JP1") (pin "3") (pinfunction "3_3") (pintype "passive"))
      (node (ref "JP9") (pin "14") (pinfunction "14_14") (pintype "passive"))
    )
    (net (code "23") (name "/PA2-2") (class "Default")
      (node (ref "JP10") (pin "15") (pinfunction "15_15") (pintype "passive"))
      (node (ref "JP2") (pin "2") (pinfunction "2_2") (pintype "passive"))
    )
    (net (code "24") (name "/PA2-3") (class "Default")
      (node (ref "JP11") (pin "15") (pinfunction "15_15") (pintype "passive"))
      (node (ref "JP15") (pin "2") (pinfunction "2_2") (pintype "passive"))
    )
    (net (code "25") (name "/PA3-2") (class "Default")
      (node (ref "JP10") (pin "16") (pinfunction "16_16") (pintype "passive"))
      (node (ref "JP2") (pin "1") (pinfunction "1_1") (pintype "passive"))
    )
    (net (code "26") (name "/PA3-3") (class "Default")
      (node (ref "JP11") (pin "16") (pinfunction "16_16") (pintype "passive"))
      (node (ref "JP15") (pin "1") (pinfunction "1_1") (pintype "passive"))
    )
    (net (code "27") (name "/PA3_1") (class "Default")
      (node (ref "JP1") (pin "1") (pinfunction "1_1") (pintype "passive"))
      (node (ref "JP9") (pin "16") (pinfunction "16_16") (pintype "passive"))
    )
    (net (code "28") (name "/SPI1_CS") (class "Default")
      (node (ref "JP10") (pin "17") (pinfunction "17_17") (pintype "passive"))
      (node (ref "JP11") (pin "17") (pinfunction "17_17") (pintype "passive"))
      (node (ref "JP9") (pin "17") (pinfunction "17_17") (pintype "passive"))
      (node (ref "X7") (pin "9") (pinfunction "KL_9") (pintype "passive"))
    )
    (net (code "29") (name "/SPI1_MISO") (class "Default")
      (node (ref "JP10") (pin "19") (pinfunction "19_19") (pintype "passive"))
      (node (ref "JP11") (pin "19") (pinfunction "19_19") (pintype "passive"))
      (node (ref "JP9") (pin "19") (pinfunction "19_19") (pintype "passive"))
      (node (ref "R208") (pin "1") (pinfunction "1_1") (pintype "passive"))
    )
    (net (code "30") (name "/SPI1_MOSI") (class "Default")
      (node (ref "JP10") (pin "20") (pinfunction "20_20") (pintype "passive"))
      (node (ref "JP11") (pin "20") (pinfunction "20_20") (pintype "passive"))
      (node (ref "JP9") (pin "20") (pinfunction "20_20") (pintype "passive"))
      (node (ref "X7") (pin "12") (pinfunction "KL_12") (pintype "passive"))
    )
    (net (code "31") (name "/SPI1_SCK") (class "Default")
      (node (ref "JP10") (pin "18") (pinfunction "18_18") (pintype "passive"))
      (node (ref "JP11") (pin "18") (pinfunction "18_18") (pintype "passive"))
      (node (ref "JP9") (pin "18") (pinfunction "18_18") (pintype "passive"))
      (node (ref "X7") (pin "10") (pinfunction "KL_10") (pintype "passive"))
    )
    (net (code "32") (name "/SPI2_CS") (class "Default")
      (node (ref "JP6") (pin "3") (pinfunction "3_3") (pintype "passive"))
      (node (ref "JP7") (pin "3") (pinfunction "3_3") (pintype "passive"))
      (node (ref "JP8") (pin "3") (pinfunction "3_3") (pintype "passive"))
      (node (ref "X7") (pin "13") (pinfunction "KL_13") (pintype "passive"))
    )
    (net (code "33") (name "/SPI2_MISO") (class "Default")
      (node (ref "JP6") (pin "5") (pinfunction "5_5") (pintype "passive"))
      (node (ref "JP7") (pin "5") (pinfunction "5_5") (pintype "passive"))
      (node (ref "JP8") (pin "5") (pinfunction "5_5") (pintype "passive"))
      (node (ref "R209") (pin "1") (pinfunction "1_1") (pintype "passive"))
    )
    (net (code "34") (name "/SPI2_MOSI") (class "Default")
      (node (ref "JP6") (pin "6") (pinfunction "6_6") (pintype "passive"))
      (node (ref "JP7") (pin "6") (pinfunction "6_6") (pintype "passive"))
      (node (ref "JP8") (pin "6") (pinfunction "6_6") (pintype "passive"))
      (node (ref "X7") (pin "16") (pinfunction "KL_16") (pintype "passive"))
    )
    (net (code "35") (name "/SPI2_SCK") (class "Default")
      (node (ref "JP6") (pin "4") (pinfunction "4_4") (pintype "passive"))
      (node (ref "JP7") (pin "4") (pinfunction "4_4") (pintype "passive"))
      (node (ref "JP8") (pin "4") (pinfunction "4_4") (pintype "passive"))
      (node (ref "X7") (pin "14") (pinfunction "KL_14") (pintype "passive"))
    )
    (net (code "36") (name "/SPI5_CS") (class "Default")
      (node (ref "JP10") (pin "9") (pinfunction "9_9") (pintype "passive"))
      (node (ref "JP11") (pin "9") (pinfunction "9_9") (pintype "passive"))
      (node (ref "JP9") (pin "9") (pinfunction "9_9") (pintype "passive"))
      (node (ref "X7") (pin "5") (pinfunction "KL_5") (pintype "passive"))
    )
    (net (code "37") (name "/SPI5_MISO") (class "Default")
      (node (ref "JP10") (pin "7") (pinfunction "7_7") (pintype "passive"))
      (node (ref "JP11") (pin "7") (pinfunction "7_7") (pintype "passive"))
      (node (ref "JP9") (pin "7") (pinfunction "7_7") (pintype "passive"))
      (node (ref "R112") (pin "1") (pinfunction "1_1") (pintype "passive"))
    )
    (net (code "38") (name "/SPI5_MOSI") (class "Default")
      (node (ref "JP10") (pin "8") (pinfunction "8_8") (pintype "passive"))
      (node (ref "JP11") (pin "8") (pinfunction "8_8") (pintype "passive"))
      (node (ref "JP9") (pin "8") (pinfunction "8_8") (pintype "passive"))
      (node (ref "X7") (pin "8") (pinfunction "KL_8") (pintype "passive"))
    )
    (net (code "39") (name "/SPI5_SCK") (class "Default")
      (node (ref "JP10") (pin "10") (pinfunction "10_10") (pintype "passive"))
      (node (ref "JP11") (pin "10") (pinfunction "10_10") (pintype "passive"))
      (node (ref "JP9") (pin "10") (pinfunction "10_10") (pintype "passive"))
      (node (ref "X7") (pin "6") (pinfunction "KL_6") (pintype "passive"))
    )
    (net (code "40") (name "/TOUCH1") (class "Default")
      (node (ref "X6") (pin "1") (pinfunction "KL_1") (pintype "passive"))
    )
    (net (code "41") (name "/TOUCH2") (class "Default")
      (node (ref "X6") (pin "2") (pinfunction "KL_2") (pintype "passive"))
    )
    (net (code "42") (name "/TOUCH3") (class "Default")
      (node (ref "X6") (pin "3") (pinfunction "KL_3") (pintype "passive"))
    )
    (net (code "43") (name "/TOUCH4") (class "Default")
      (node (ref "X6") (pin "4") (pinfunction "KL_4") (pintype "passive"))
    )
    (net (code "44") (name "/TOUCH5") (class "Default")
      (node (ref "X6") (pin "5") (pinfunction "KL_5") (pintype "passive"))
    )
    (net (code "45") (name "/TOUCH6") (class "Default")
      (node (ref "X6") (pin "6") (pinfunction "KL_6") (pintype "passive"))
    )
    (net (code "46") (name "/TOUCH7") (class "Default")
      (node (ref "X6") (pin "7") (pinfunction "KL_7") (pintype "passive"))
    )
    (net (code "47") (name "/TOUCH8") (class "Default")
      (node (ref "X6") (pin "8") (pinfunction "KL_8") (pintype "passive"))
    )
    (net (code "48") (name "/TOUCH9") (class "Default")
      (node (ref "X6") (pin "9") (pinfunction "KL_9") (pintype "passive"))
    )
    (net (code "49") (name "/TOUCH10") (class "Default")
      (node (ref "X6") (pin "10") (pinfunction "KL_10") (pintype "passive"))
    )
    (net (code "50") (name "/TOUCH11") (class "Default")
      (node (ref "X6") (pin "11") (pinfunction "KL_11") (pintype "passive"))
    )
    (net (code "51") (name "/TOUCH12") (class "Default")
      (node (ref "X6") (pin "12") (pinfunction "KL_12") (pintype "passive"))
    )
    (net (code "52") (name "3V3D3") (class "Default")
      (node (ref "C162") (pin "1") (pinfunction "1_1") (pintype "passive"))
      (node (ref "C164") (pin "1") (pinfunction "1_1") (pintype "passive"))
      (node (ref "J1") (pin "3") (pinfunction "3_3") (pintype "bidirectional"))
      (node (ref "J3") (pin "3") (pinfunction "3_3") (pintype "bidirectional"))
      (node (ref "JP12") (pin "2") (pinfunction "2_2") (pintype "passive"))
      (node (ref "JP13") (pin "2") (pinfunction "2_2") (pintype "passive"))
      (node (ref "JP16") (pin "2") (pinfunction "2_2") (pintype "passive"))
      (node (ref "JP17") (pin "2") (pinfunction "2_2") (pintype "passive"))
      (node (ref "JP18") (pin "2") (pinfunction "2_2") (pintype "passive"))
      (node (ref "JP19") (pin "2") (pinfunction "2_2") (pintype "passive"))
      (node (ref "JP20") (pin "2") (pinfunction "2_2") (pintype "passive"))
      (node (ref "JP21") (pin "2") (pinfunction "2_2") (pintype "passive"))
      (node (ref "L1") (pin "2") (pinfunction "2_2") (pintype "passive"))
      (node (ref "R125") (pin "1") (pinfunction "1_1") (pintype "passive"))
      (node (ref "R134") (pin "2") (pinfunction "2_2") (pintype "passive"))
      (node (ref "U20") (pin "24") (pinfunction "VCC_24") (pintype "power_in"))
    )
    (net (code "53") (name "AGND1") (class "Default")
      (node (ref "C15") (pin "2") (pinfunction "2_2") (pintype "passive"))
      (node (ref "C16") (pin "2") (pinfunction "2_2") (pintype "passive"))
      (node (ref "C20") (pin "2") (pinfunction "2_2") (pintype "passive"))
      (node (ref "C21") (pin "2") (pinfunction "2_2") (pintype "passive"))
      (node (ref "C22") (pin "2") (pinfunction "2_2") (pintype "passive"))
      (node (ref "C23") (pin "2") (pinfunction "2_2") (pintype "passive"))
      (node (ref "C24") (pin "2") (pinfunction "2_2") (pintype "passive"))
      (node (ref "C25") (pin "2") (pinfunction "2_2") (pintype "passive"))
      (node (ref "C26") (pin "2") (pinfunction "2_2") (pintype "passive"))
      (node (ref "C27") (pin "2") (pinfunction "2_2") (pintype "passive"))
      (node (ref "JP26") (pin "1") (pinfunction "1_1") (pintype "passive"))
      (node (ref "L2") (pin "1") (pinfunction "1_1") (pintype "passive"))
      (node (ref "U1") (pin "15") (pinfunction "GND_15") (pintype "power_in"))
      (node (ref "VR1") (pin "P$3") (pinfunction "A_P$3") (pintype "passive"))
      (node (ref "VR2") (pin "P$3") (pinfunction "A_P$3") (pintype "passive"))
      (node (ref "VR3") (pin "P$3") (pinfunction "A_P$3") (pintype "passive"))
      (node (ref "VR4") (pin "P$3") (pinfunction "A_P$3") (pintype "passive"))
      (node (ref "VR5") (pin "P$3") (pinfunction "A_P$3") (pintype "passive"))
      (node (ref "VR6") (pin "P$3") (pinfunction "A_P$3") (pintype "passive"))
      (node (ref "VR7") (pin "P$3") (pinfunction "A_P$3") (pintype "passive"))
      (node (ref "VR8") (pin "P$3") (pinfunction "A_P$3") (pintype "passive"))
    )
    (net (code "54") (name "AGND3") (class "Default")
      (node (ref "JP22") (pin "2") (pinfunction "2_2") (pintype "passive"))
      (node (ref "JP23") (pin "2") (pinfunction "2_2") (pintype "passive"))
      (node (ref "JP24") (pin "2") (pinfunction "2_2") (pintype "passive"))
      (node (ref "JP25") (pin "2") (pinfunction "2_2") (pintype "passive"))
      (node (ref "X6") (pin "13") (pinfunction "KL_13") (pintype "passive"))
      (node (ref "X6") (pin "14") (pinfunction "KL_14") (pintype "passive"))
      (node (ref "X6") (pin "15") (pinfunction "KL_15") (pintype "passive"))
      (node (ref "X6") (pin "16") (pinfunction "KL_16") (pintype "passive"))
    )
    (net (code "55") (name "AGND5") (class "Default")
      (node (ref "C10") (pin "1") (pinfunction "1_1") (pintype "passive"))
      (node (ref "C5") (pin "2") (pinfunction "2_2") (pintype "passive"))
      (node (ref "C51") (pin "2") (pinfunction "2_2") (pintype "passive"))
      (node (ref "C52") (pin "1") (pinfunction "1_1") (pintype "passive"))
      (node (ref "C53") (pin "2") (pinfunction "2_2") (pintype "passive"))
      (node (ref "C54") (pin "1") (pinfunction "1_1") (pintype "passive"))
      (node (ref "C6") (pin "1") (pinfunction "1_1") (pintype "passive"))
      (node (ref "C7") (pin "2") (pinfunction "2_2") (pintype "passive"))
      (node (ref "C8") (pin "1") (pinfunction "1_1") (pintype "passive"))
      (node (ref "C9") (pin "2") (pinfunction "2_2") (pintype "passive"))
      (node (ref "FB_IN") (pin "SLEEVE") (pinfunction "SLEEVE_SLEEVE") (pintype "bidirectional"))
      (node (ref "IC1") (pin "10") (pinfunction "+IN_10") (pintype "input"))
      (node (ref "IC1") (pin "12") (pinfunction "+IN_12") (pintype "input"))
      (node (ref "IC1") (pin "3") (pinfunction "+IN_3") (pintype "input"))
      (node (ref "IC5") (pin "GND") (pinfunction "GND_GND") (pintype "input"))
      (node (ref "IC6") (pin "GND") (pinfunction "GND_GND") (pintype "input"))
      (node (ref "J2") (pin "4") (pinfunction "4_4") (pintype "bidirectional"))
      (node (ref "J36") (pin "3") (pinfunction "3_3") (pintype "bidirectional"))
      (node (ref "J36") (pin "4") (pinfunction "4_4") (pintype "bidirectional"))
      (node (ref "JP14") (pin "2") (pinfunction "2_2") (pintype "passive"))
      (node (ref "JP3") (pin "3") (pinfunction "3_3") (pintype "passive"))
      (node (ref "JP3") (pin "4") (pinfunction "4_4") (pintype "passive"))
      (node (ref "JP3") (pin "5") (pinfunction "5_5") (pintype "passive"))
      (node (ref "JP3") (pin "6") (pinfunction "6_6") (pintype "passive"))
      (node (ref "JP4") (pin "3") (pinfunction "3_3") (pintype "passive"))
      (node (ref "JP4") (pin "4") (pinfunction "4_4") (pintype "passive"))
      (node (ref "JP4") (pin "5") (pinfunction "5_5") (pintype "passive"))
      (node (ref "JP4") (pin "6") (pinfunction "6_6") (pintype "passive"))
      (node (ref "JP5") (pin "3") (pinfunction "3_3") (pintype "passive"))
      (node (ref "JP5") (pin "4") (pinfunction "4_4") (pintype "passive"))
      (node (ref "JP5") (pin "5") (pinfunction "5_5") (pintype "passive"))
      (node (ref "JP5") (pin "6") (pinfunction "6_6") (pintype "passive"))
      (node (ref "MONO_OUT") (pin "SLEEVE") (pinfunction "SLEEVE_SLEEVE") (pintype "bidirectional"))
      (node (ref "R11") (pin "1") (pinfunction "1_1") (pintype "passive"))
      (node (ref "R185") (pin "2") (pinfunction "2_2") (pintype "passive"))
      (node (ref "STEREO_OUT") (pin "SLEEVE") (pinfunction "SLEEVE_SLEEVE") (pintype "bidirectional"))
      (node (ref "U$3") (pin "P$4") (pinfunction "0_P$4") (pintype "bidirectional"))
    )
    (net (code "56") (name "DGND4") (class "Default")
      (node (ref "C1") (pin "2") (pinfunction "2_2") (pintype "passive"))
      (node (ref "C119") (pin "2") (pinfunction "2_2") (pintype "passive"))
      (node (ref "C12") (pin "2") (pinfunction "2_2") (pintype "passive"))
      (node (ref "C120") (pin "2") (pinfunction "2_2") (pintype "passive"))
      (node (ref "C13") (pin "2") (pinfunction "2_2") (pintype "passive"))
      (node (ref "C14") (pin "2") (pinfunction "2_2") (pintype "passive"))
      (node (ref "C17") (pin "2") (pinfunction "2_2") (pintype "passive"))
      (node (ref "C18") (pin "2") (pinfunction "2_2") (pintype "passive"))
      (node (ref "C19") (pin "2") (pinfunction "2_2") (pintype "passive"))
      (node (ref "C2") (pin "2") (pinfunction "2_2") (pintype "passive"))
      (node (ref "C3") (pin "2") (pinfunction "2_2") (pintype "passive"))
      (node (ref "C4") (pin "2") (pinfunction "2_2") (pintype "passive"))
      (node (ref "DGND1") (pin "1") (pinfunction "1_1") (pintype "passive"))
      (node (ref "DGND2") (pin "1") (pinfunction "1_1") (pintype "passive"))
      (node (ref "DGND5") (pin "1") (pinfunction "1_1") (pintype "passive"))
      (node (ref "JP10") (pin "24") (pinfunction "24_24") (pintype "passive"))
      (node (ref "JP11") (pin "22") (pinfunction "22_22") (pintype "passive"))
      (node (ref "JP6") (pin "20") (pinfunction "20_20") (pintype "passive"))
      (node (ref "JP7") (pin "20") (pinfunction "20_20") (pintype "passive"))
      (node (ref "JP8") (pin "20") (pinfunction "20_20") (pintype "passive"))
      (node (ref "JP9") (pin "22") (pinfunction "22_22") (pintype "passive"))
      (node (ref "JP9") (pin "24") (pinfunction "24_24") (pintype "passive"))
      (node (ref "R111") (pin "2") (pinfunction "2_2") (pintype "passive"))
      (node (ref "R185") (pin "1") (pinfunction "1_1") (pintype "passive"))
      (node (ref "U15") (pin "GND") (pinfunction "GND_GND") (pintype "input"))
      (node (ref "U17") (pin "GND") (pinfunction "GND_GND") (pintype "input"))
      (node (ref "U2") (pin "GND") (pinfunction "GND_GND") (pintype "input"))
      (node (ref "X7") (pin "2") (pinfunction "KL_2") (pintype "passive"))
      (node (ref "X7") (pin "4") (pinfunction "KL_4") (pintype "passive"))
    )
    (net (code "57") (name "GND-ISO") (class "Default")
      (node (ref "C162") (pin "2") (pinfunction "2_2") (pintype "passive"))
      (node (ref "C164") (pin "2") (pinfunction "2_2") (pintype "passive"))
      (node (ref "J1") (pin "4") (pinfunction "4_4") (pintype "bidirectional"))
      (node (ref "J3") (pin "4") (pinfunction "4_4") (pintype "bidirectional"))
      (node (ref "JP12") (pin "1") (pinfunction "1_1") (pintype "passive"))
      (node (ref "JP13") (pin "1") (pinfunction "1_1") (pintype "passive"))
      (node (ref "JP16") (pin "1") (pinfunction "1_1") (pintype "passive"))
      (node (ref "JP17") (pin "1") (pinfunction "1_1") (pintype "passive"))
      (node (ref "JP18") (pin "1") (pinfunction "1_1") (pintype "passive"))
      (node (ref "JP19") (pin "1") (pinfunction "1_1") (pintype "passive"))
      (node (ref "JP20") (pin "1") (pinfunction "1_1") (pintype "passive"))
      (node (ref "JP21") (pin "1") (pinfunction "1_1") (pintype "passive"))
      (node (ref "L2") (pin "2") (pinfunction "2_2") (pintype "passive"))
      (node (ref "R128") (pin "2") (pinfunction "2_2") (pintype "passive"))
      (node (ref "R129") (pin "2") (pinfunction "2_2") (pintype "passive"))
      (node (ref "S1") (pin "3") (pinfunction "2_3") (pintype "passive"))
      (node (ref "S2") (pin "3") (pinfunction "2_3") (pintype "passive"))
      (node (ref "U20") (pin "1") (pinfunction "A0_1") (pintype "input"))
      (node (ref "U20") (pin "12") (pinfunction "GND_12") (pintype "power_in"))
      (node (ref "U20") (pin "21") (pinfunction "A2_21") (pintype "input"))
    )
    (net (code "58") (name "MONO_OUTPUT") (class "Default")
      (node (ref "C158") (pin "+") (pinfunction "+_+") (pintype "passive"))
      (node (ref "IC1") (pin "1") (pinfunction "OUT_1") (pintype "output"))
      (node (ref "R159") (pin "2") (pinfunction "2_2") (pintype "passive"))
      (node (ref "R4") (pin "1") (pinfunction "1_1") (pintype "passive"))
    )
    (net (code "59") (name "Net-(3V3A_0A-Pad1)") (class "Default")
      (node (ref "3V3A_0A") (pin "1") (pinfunction "1_1") (pintype "passive"))
      (node (ref "JP10") (pin "12") (pinfunction "12_12") (pintype "passive"))
    )
    (net (code "60") (name "Net-(3V3A_0B-Pad1)") (class "Default")
      (node (ref "3V3A_0B") (pin "1") (pinfunction "1_1") (pintype "passive"))
      (node (ref "JP11") (pin "12") (pinfunction "12_12") (pintype "passive"))
    )
    (net (code "61") (name "Net-(3V3A_0C-Pad1)") (class "Default")
      (node (ref "3V3A_0C") (pin "1") (pinfunction "1_1") (pintype "passive"))
      (node (ref "JP9") (pin "12") (pinfunction "12_12") (pintype "passive"))
    )
    (net (code "62") (name "Net-(C158-Pad-)") (class "Default")
      (node (ref "C158") (pin "-") (pinfunction "-_-") (pintype "passive"))
      (node (ref "R10") (pin "1") (pinfunction "1_1") (pintype "passive"))
    )
    (net (code "63") (name "Net-(IC1A--IN)") (class "Default")
      (node (ref "IC1") (pin "2") (pinfunction "-IN_2") (pintype "input"))
      (node (ref "R159") (pin "1") (pinfunction "1_1") (pintype "passive"))
      (node (ref "R160") (pin "2") (pinfunction "2_2") (pintype "passive"))
      (node (ref "R161") (pin "2") (pinfunction "2_2") (pintype "passive"))
      (node (ref "R162") (pin "2") (pinfunction "2_2") (pintype "passive"))
    )
    (net (code "64") (name "Net-(IC1B-+IN)") (class "Default")
      (node (ref "FB_IN") (pin "TIP") (pinfunction "TIP_TIP") (pintype "bidirectional"))
      (node (ref "IC1") (pin "5") (pinfunction "+IN_5") (pintype "input"))
      (node (ref "J2") (pin "3") (pinfunction "3_3") (pintype "bidirectional"))
    )
    (net (code "65") (name "Net-(IC1C--IN)") (class "Default")
      (node (ref "IC1") (pin "9") (pinfunction "-IN_9") (pintype "input"))
      (node (ref "R33") (pin "2") (pinfunction "2_2") (pintype "passive"))
      (node (ref "R37") (pin "1") (pinfunction "1_1") (pintype "passive"))
      (node (ref "R5") (pin "2") (pinfunction "2_2") (pintype "passive"))
    )
    (net (code "66") (name "Net-(IC1C-OUT)") (class "Default")
      (node (ref "IC1") (pin "8") (pinfunction "OUT_8") (pintype "output"))
      (node (ref "J2") (pin "1") (pinfunction "1_1") (pintype "bidirectional"))
      (node (ref "R37") (pin "2") (pinfunction "2_2") (pintype "passive"))
      (node (ref "STEREO_OUT") (pin "RING") (pinfunction "RING_RING") (pintype "bidirectional"))
    )
    (net (code "67") (name "Net-(IC1D--IN)") (class "Default")
      (node (ref "IC1") (pin "13") (pinfunction "-IN_13") (pintype "input"))
      (node (ref "R34") (pin "2") (pinfunction "2_2") (pintype "passive"))
      (node (ref "R35") (pin "2") (pinfunction "2_2") (pintype "passive"))
      (node (ref "R38") (pin "1") (pinfunction "1_1") (pintype "passive"))
    )
    (net (code "68") (name "Net-(IC1D-OUT)") (class "Default")
      (node (ref "IC1") (pin "14") (pinfunction "OUT_14") (pintype "output"))
      (node (ref "J2") (pin "2") (pinfunction "2_2") (pintype "bidirectional"))
      (node (ref "R38") (pin "2") (pinfunction "2_2") (pintype "passive"))
      (node (ref "STEREO_OUT") (pin "TIP") (pinfunction "TIP_TIP") (pintype "bidirectional"))
    )
    (net (code "69") (name "Net-(J4-Pad1)") (class "Default")
      (node (ref "J4") (pin "1") (pinfunction "1_1") (pintype "bidirectional"))
      (node (ref "S1") (pin "1") (pinfunction "1_1") (pintype "passive"))
    )
    (net (code "70") (name "Net-(J4-Pad2)") (class "Default")
      (node (ref "J4") (pin "2") (pinfunction "2_2") (pintype "bidirectional"))
      (node (ref "S2") (pin "1") (pinfunction "1_1") (pintype "passive"))
    )
    (net (code "71") (name "Net-(J4-Pad3)") (class "Default")
      (node (ref "J4") (pin "3") (pinfunction "3_3") (pintype "bidirectional"))
      (node (ref "LED5") (pin "A") (pinfunction "A_A") (pintype "passive"))
    )
    (net (code "72") (name "Net-(J4-Pad4)") (class "Default")
      (node (ref "J4") (pin "4") (pinfunction "4_4") (pintype "bidirectional"))
      (node (ref "LED6") (pin "A") (pinfunction "A_A") (pintype "passive"))
    )
    (net (code "73") (name "Net-(J36-Pad1)") (class "Default")
      (node (ref "J36") (pin "1") (pinfunction "1_1") (pintype "bidirectional"))
      (node (ref "J36") (pin "2") (pinfunction "2_2") (pintype "bidirectional"))
      (node (ref "JP14") (pin "1") (pinfunction "1_1") (pintype "passive"))
      (node (ref "MONO_OUT") (pin "TIP") (pinfunction "TIP_TIP") (pintype "bidirectional"))
      (node (ref "R10") (pin "2") (pinfunction "2_2") (pintype "passive"))
      (node (ref "R11") (pin "2") (pinfunction "2_2") (pintype "passive"))
    )
    (net (code "74") (name "Net-(JP1-Pad2)") (class "Default")
      (node (ref "JP1") (pin "2") (pinfunction "2_2") (pintype "passive"))
      (node (ref "JP9") (pin "15") (pinfunction "15_15") (pintype "passive"))
    )
    (net (code "75") (name "Net-(JP1-Pad4)") (class "Default")
      (node (ref "JP1") (pin "4") (pinfunction "4_4") (pintype "passive"))
      (node (ref "JP9") (pin "13") (pinfunction "13_13") (pintype "passive"))
    )
    (net (code "76") (name "Net-(LED5-PadC)") (class "Default")
      (node (ref "LED5") (pin "C") (pinfunction "C_C") (pintype "passive"))
      (node (ref "R128") (pin "1") (pinfunction "1_1") (pintype "passive"))
    )
    (net (code "77") (name "Net-(LED6-PadC)") (class "Default")
      (node (ref "LED6") (pin "C") (pinfunction "C_C") (pintype "passive"))
      (node (ref "R129") (pin "1") (pinfunction "1_1") (pintype "passive"))
    )
    (net (code "78") (name "Net-(U$3-VIN+)") (class "Default")
      (node (ref "C11") (pin "1") (pinfunction "1_1") (pintype "passive"))
      (node (ref "C121") (pin "1") (pinfunction "1_1") (pintype "passive"))
      (node (ref "R110") (pin "1") (pinfunction "1_1") (pintype "passive"))
      (node (ref "U$3") (pin "P$1") (pinfunction "VIN+_P$1") (pintype "bidirectional"))
      (node (ref "VREGIN") (pin "1") (pinfunction "1_1") (pintype "passive"))
    )
    (net (code "79") (name "Net-(U$3-VIN-)") (class "Default")
      (node (ref "C11") (pin "2") (pinfunction "2_2") (pintype "passive"))
      (node (ref "C121") (pin "2") (pinfunction "2_2") (pintype "passive"))
      (node (ref "R111") (pin "1") (pinfunction "1_1") (pintype "passive"))
      (node (ref "U$3") (pin "P$2") (pinfunction "VIN-_P$2") (pintype "bidirectional"))
      (node (ref "VREGGND") (pin "1") (pinfunction "1_1") (pintype "passive"))
    )
    (net (code "80") (name "Net-(U1-AIN0)") (class "Default")
      (node (ref "C15") (pin "1") (pinfunction "1_1") (pintype "passive"))
      (node (ref "U1") (pin "5") (pinfunction "AIN0_5") (pintype "input"))
      (node (ref "VR1") (pin "P$2") (pinfunction "S_P$2") (pintype "passive"))
    )
    (net (code "81") (name "Net-(U1-AIN1)") (class "Default")
      (node (ref "C16") (pin "1") (pinfunction "1_1") (pintype "passive"))
      (node (ref "U1") (pin "6") (pinfunction "AIN1_6") (pintype "input"))
      (node (ref "VR2") (pin "P$2") (pinfunction "S_P$2") (pintype "passive"))
    )
    (net (code "82") (name "Net-(U1-AIN2)") (class "Default")
      (node (ref "C21") (pin "1") (pinfunction "1_1") (pintype "passive"))
      (node (ref "U1") (pin "7") (pinfunction "AIN2_7") (pintype "input"))
      (node (ref "VR3") (pin "P$2") (pinfunction "S_P$2") (pintype "passive"))
    )
    (net (code "83") (name "Net-(U1-AIN3)") (class "Default")
      (node (ref "C22") (pin "1") (pinfunction "1_1") (pintype "passive"))
      (node (ref "U1") (pin "8") (pinfunction "AIN3_8") (pintype "input"))
      (node (ref "VR4") (pin "P$2") (pinfunction "S_P$2") (pintype "passive"))
    )
    (net (code "84") (name "Net-(U1-AIN4)") (class "Default")
      (node (ref "C24") (pin "1") (pinfunction "1_1") (pintype "passive"))
      (node (ref "U1") (pin "9") (pinfunction "AIN4_9") (pintype "input"))
      (node (ref "VR5") (pin "P$2") (pinfunction "S_P$2") (pintype "passive"))
    )
    (net (code "85") (name "Net-(U1-AIN5)") (class "Default")
      (node (ref "C25") (pin "1") (pinfunction "1_1") (pintype "passive"))
      (node (ref "U1") (pin "10") (pinfunction "AIN5_10") (pintype "input"))
      (node (ref "VR6") (pin "P$2") (pinfunction "S_P$2") (pintype "passive"))
    )
    (net (code "86") (name "Net-(U1-AIN6)") (class "Default")
      (node (ref "C26") (pin "1") (pinfunction "1_1") (pintype "passive"))
      (node (ref "U1") (pin "11") (pinfunction "AIN6_11") (pintype "input"))
      (node (ref "VR7") (pin "P$2") (pinfunction "S_P$2") (pintype "passive"))
    )
    (net (code "87") (name "Net-(U1-AIN7)") (class "Default")
      (node (ref "C27") (pin "1") (pinfunction "1_1") (pintype "passive"))
      (node (ref "U1") (pin "12") (pinfunction "AIN7_12") (pintype "input"))
      (node (ref "VR8") (pin "P$2") (pinfunction "S_P$2") (pintype "passive"))
    )
    (net (code "88") (name "Net-(U20-A1)") (class "Default")
      (node (ref "R125") (pin "2") (pinfunction "2_2") (pintype "passive"))
      (node (ref "U20") (pin "2") (pinfunction "A1_2") (pintype "input"))
    )
    (net (code "89") (name "Net-(U20-~{RESET})") (class "Default")
      (node (ref "R134") (pin "1") (pinfunction "1_1") (pintype "passive"))
      (node (ref "U20") (pin "3") (pinfunction "~{RESET}_3") (pintype "input"))
    )
    (net (code "90") (name "Net-(X6I-KL)") (class "Default")
      (node (ref "JP22") (pin "1") (pinfunction "1_1") (pintype "passive"))
      (node (ref "X6") (pin "17") (pinfunction "KL_17") (pintype "passive"))
    )
    (net (code "91") (name "Net-(X6J-KL)") (class "Default")
      (node (ref "JP23") (pin "1") (pinfunction "1_1") (pintype "passive"))
      (node (ref "X6") (pin "18") (pinfunction "KL_18") (pintype "passive"))
    )
    (net (code "92") (name "Net-(X6K-KL)") (class "Default")
      (node (ref "JP24") (pin "1") (pinfunction "1_1") (pintype "passive"))
      (node (ref "X6") (pin "19") (pinfunction "KL_19") (pintype "passive"))
    )
    (net (code "93") (name "Net-(X6M-KL)") (class "Default")
      (node (ref "JP25") (pin "1") (pinfunction "1_1") (pintype "passive"))
      (node (ref "X6") (pin "20") (pinfunction "KL_20") (pintype "passive"))
    )
    (net (code "94") (name "Net-(X7C-KL)") (class "Default")
      (node (ref "R208") (pin "2") (pinfunction "2_2") (pintype "passive"))
      (node (ref "X7") (pin "11") (pinfunction "KL_11") (pintype "passive"))
    )
    (net (code "95") (name "Net-(X7G-KL)") (class "Default")
      (node (ref "R209") (pin "2") (pinfunction "2_2") (pintype "passive"))
      (node (ref "X7") (pin "15") (pinfunction "KL_15") (pintype "passive"))
    )
    (net (code "96") (name "Net-(X7N-KL)") (class "Default")
      (node (ref "R112") (pin "2") (pinfunction "2_2") (pintype "passive"))
      (node (ref "X7") (pin "7") (pinfunction "KL_7") (pintype "passive"))
    )
    (net (code "97") (name "REG+12V") (class "Default")
      (node (ref "+15VA") (pin "1") (pinfunction "1_1") (pintype "passive"))
      (node (ref "C53") (pin "1") (pinfunction "1_1") (pintype "passive"))
      (node (ref "C9") (pin "1") (pinfunction "1_1") (pintype "passive"))
      (node (ref "IC5") (pin "IN") (pinfunction "IN_IN") (pintype "input"))
      (node (ref "U$3") (pin "P$5") (pinfunction "12VOUT_P$5") (pintype "bidirectional"))
    )
    (net (code "98") (name "REG-12V") (class "Default")
      (node (ref "-15VA") (pin "1") (pinfunction "1_1") (pintype "passive"))
      (node (ref "C10") (pin "2") (pinfunction "2_2") (pintype "passive"))
      (node (ref "C54") (pin "2") (pinfunction "2_2") (pintype "passive"))
      (node (ref "IC6") (pin "IN") (pinfunction "IN_IN") (pintype "input"))
      (node (ref "U$3") (pin "P$3") (pinfunction "-12VOUT_P$3") (pintype "bidirectional"))
    )
    (net (code "99") (name "SC0") (class "Default")
      (node (ref "JP12") (pin "3") (pinfunction "3_3") (pintype "passive"))
      (node (ref "U20") (pin "5") (pinfunction "SC0_5") (pintype "bidirectional"))
    )
    (net (code "100") (name "SC1") (class "Default")
      (node (ref "JP13") (pin "3") (pinfunction "3_3") (pintype "passive"))
      (node (ref "U20") (pin "7") (pinfunction "SC1_7") (pintype "bidirectional"))
    )
    (net (code "101") (name "SC2") (class "Default")
      (node (ref "JP16") (pin "3") (pinfunction "3_3") (pintype "passive"))
      (node (ref "U20") (pin "9") (pinfunction "SC2_9") (pintype "bidirectional"))
    )
    (net (code "102") (name "SC3") (class "Default")
      (node (ref "JP17") (pin "3") (pinfunction "3_3") (pintype "passive"))
      (node (ref "U20") (pin "11") (pinfunction "SC3_11") (pintype "bidirectional"))
    )
    (net (code "103") (name "SC4") (class "Default")
      (node (ref "JP18") (pin "3") (pinfunction "3_3") (pintype "passive"))
      (node (ref "U20") (pin "14") (pinfunction "SC4_14") (pintype "bidirectional"))
    )
    (net (code "104") (name "SC5") (class "Default")
      (node (ref "JP19") (pin "3") (pinfunction "3_3") (pintype "passive"))
      (node (ref "U20") (pin "16") (pinfunction "SC5_16") (pintype "bidirectional"))
    )
    (net (code "105") (name "SC6") (class "Default")
      (node (ref "JP20") (pin "3") (pinfunction "3_3") (pintype "passive"))
      (node (ref "U20") (pin "18") (pinfunction "SC6_18") (pintype "bidirectional"))
    )
    (net (code "106") (name "SC7") (class "Default")
      (node (ref "JP21") (pin "3") (pinfunction "3_3") (pintype "passive"))
      (node (ref "U20") (pin "20") (pinfunction "SC7_20") (pintype "bidirectional"))
    )
    (net (code "107") (name "SD0") (class "Default")
      (node (ref "JP12") (pin "4") (pinfunction "4_4") (pintype "passive"))
      (node (ref "U20") (pin "4") (pinfunction "SD0_4") (pintype "bidirectional"))
    )
    (net (code "108") (name "SD1") (class "Default")
      (node (ref "JP13") (pin "4") (pinfunction "4_4") (pintype "passive"))
      (node (ref "U20") (pin "6") (pinfunction "SD1_6") (pintype "bidirectional"))
    )
    (net (code "109") (name "SD2") (class "Default")
      (node (ref "JP16") (pin "4") (pinfunction "4_4") (pintype "passive"))
      (node (ref "U20") (pin "8") (pinfunction "SD2_8") (pintype "bidirectional"))
    )
    (net (code "110") (name "SD3") (class "Default")
      (node (ref "JP17") (pin "4") (pinfunction "4_4") (pintype "passive"))
      (node (ref "U20") (pin "10") (pinfunction "SD3_10") (pintype "bidirectional"))
    )
    (net (code "111") (name "SD4") (class "Default")
      (node (ref "JP18") (pin "4") (pinfunction "4_4") (pintype "passive"))
      (node (ref "U20") (pin "13") (pinfunction "SD4_13") (pintype "bidirectional"))
    )
    (net (code "112") (name "SD5") (class "Default")
      (node (ref "JP19") (pin "4") (pinfunction "4_4") (pintype "passive"))
      (node (ref "U20") (pin "15") (pinfunction "SD5_15") (pintype "bidirectional"))
    )
    (net (code "113") (name "SD6") (class "Default")
      (node (ref "JP20") (pin "4") (pinfunction "4_4") (pintype "passive"))
      (node (ref "U20") (pin "17") (pinfunction "SD6_17") (pintype "bidirectional"))
    )
    (net (code "114") (name "SD7") (class "Default")
      (node (ref "JP21") (pin "4") (pinfunction "4_4") (pintype "passive"))
      (node (ref "U20") (pin "19") (pinfunction "SD7_19") (pintype "bidirectional"))
    )
    (net (code "115") (name "unconnected-(FB_IN-PadRING)") (class "Default")
      (node (ref "FB_IN") (pin "RING") (pinfunction "RING_RING") (pintype "bidirectional"))
    )
    (net (code "116") (name "unconnected-(FB_IN-PadRSH)") (class "Default")
      (node (ref "FB_IN") (pin "RSH") (pinfunction "RSH_RSH") (pintype "bidirectional"))
    )
    (net (code "117") (name "unconnected-(FB_IN-PadTSH)") (class "Default")
      (node (ref "FB_IN") (pin "TSH") (pinfunction "TSH_TSH") (pintype "bidirectional"))
    )
    (net (code "118") (name "unconnected-(JP6-Pad1)") (class "Default")
      (node (ref "JP6") (pin "1") (pinfunction "1_1") (pintype "passive"))
    )
    (net (code "119") (name "unconnected-(JP6-Pad2)") (class "Default")
      (node (ref "JP6") (pin "2") (pinfunction "2_2") (pintype "passive"))
    )
    (net (code "120") (name "unconnected-(JP6-Pad7)") (class "Default")
      (node (ref "JP6") (pin "7") (pinfunction "7_7") (pintype "passive"))
    )
    (net (code "121") (name "unconnected-(JP6-Pad8)") (class "Default")
      (node (ref "JP6") (pin "8") (pinfunction "8_8") (pintype "passive"))
    )
    (net (code "122") (name "unconnected-(JP6-Pad9)") (class "Default")
      (node (ref "JP6") (pin "9") (pinfunction "9_9") (pintype "passive"))
    )
    (net (code "123") (name "unconnected-(JP6-Pad10)") (class "Default")
      (node (ref "JP6") (pin "10") (pinfunction "10_10") (pintype "passive"))
    )
    (net (code "124") (name "unconnected-(JP6-Pad11)") (class "Default")
      (node (ref "JP6") (pin "11") (pinfunction "11_11") (pintype "passive"))
    )
    (net (code "125") (name "unconnected-(JP6-Pad12)") (class "Default")
      (node (ref "JP6") (pin "12") (pinfunction "12_12") (pintype "passive"))
    )
    (net (code "126") (name "unconnected-(JP6-Pad13)") (class "Default")
      (node (ref "JP6") (pin "13") (pinfunction "13_13") (pintype "passive"))
    )
    (net (code "127") (name "unconnected-(JP6-Pad14)") (class "Default")
      (node (ref "JP6") (pin "14") (pinfunction "14_14") (pintype "passive"))
    )
    (net (code "128") (name "unconnected-(JP6-Pad15)") (class "Default")
      (node (ref "JP6") (pin "15") (pinfunction "15_15") (pintype "passive"))
    )
    (net (code "129") (name "unconnected-(JP6-Pad16)") (class "Default")
      (node (ref "JP6") (pin "16") (pinfunction "16_16") (pintype "passive"))
    )
    (net (code "130") (name "unconnected-(JP6-Pad17)") (class "Default")
      (node (ref "JP6") (pin "17") (pinfunction "17_17") (pintype "passive"))
    )
    (net (code "131") (name "unconnected-(JP6-Pad18)") (class "Default")
      (node (ref "JP6") (pin "18") (pinfunction "18_18") (pintype "passive"))
    )
    (net (code "132") (name "unconnected-(JP7-Pad1)") (class "Default")
      (node (ref "JP7") (pin "1") (pinfunction "1_1") (pintype "passive"))
    )
    (net (code "133") (name "unconnected-(JP7-Pad2)") (class "Default")
      (node (ref "JP7") (pin "2") (pinfunction "2_2") (pintype "passive"))
    )
    (net (code "134") (name "unconnected-(JP7-Pad7)") (class "Default")
      (node (ref "JP7") (pin "7") (pinfunction "7_7") (pintype "passive"))
    )
    (net (code "135") (name "unconnected-(JP7-Pad8)") (class "Default")
      (node (ref "JP7") (pin "8") (pinfunction "8_8") (pintype "passive"))
    )
    (net (code "136") (name "unconnected-(JP7-Pad9)") (class "Default")
      (node (ref "JP7") (pin "9") (pinfunction "9_9") (pintype "passive"))
    )
    (net (code "137") (name "unconnected-(JP7-Pad10)") (class "Default")
      (node (ref "JP7") (pin "10") (pinfunction "10_10") (pintype "passive"))
    )
    (net (code "138") (name "unconnected-(JP7-Pad11)") (class "Default")
      (node (ref "JP7") (pin "11") (pinfunction "11_11") (pintype "passive"))
    )
    (net (code "139") (name "unconnected-(JP7-Pad12)") (class "Default")
      (node (ref "JP7") (pin "12") (pinfunction "12_12") (pintype "passive"))
    )
    (net (code "140") (name "unconnected-(JP7-Pad13)") (class "Default")
      (node (ref "JP7") (pin "13") (pinfunction "13_13") (pintype "passive"))
    )
    (net (code "141") (name "unconnected-(JP7-Pad14)") (class "Default")
      (node (ref "JP7") (pin "14") (pinfunction "14_14") (pintype "passive"))
    )
    (net (code "142") (name "unconnected-(JP7-Pad15)") (class "Default")
      (node (ref "JP7") (pin "15") (pinfunction "15_15") (pintype "passive"))
    )
    (net (code "143") (name "unconnected-(JP7-Pad16)") (class "Default")
      (node (ref "JP7") (pin "16") (pinfunction "16_16") (pintype "passive"))
    )
    (net (code "144") (name "unconnected-(JP7-Pad17)") (class "Default")
      (node (ref "JP7") (pin "17") (pinfunction "17_17") (pintype "passive"))
    )
    (net (code "145") (name "unconnected-(JP7-Pad18)") (class "Default")
      (node (ref "JP7") (pin "18") (pinfunction "18_18") (pintype "passive"))
    )
    (net (code "146") (name "unconnected-(JP8-Pad1)") (class "Default")
      (node (ref "JP8") (pin "1") (pinfunction "1_1") (pintype "passive"))
    )
    (net (code "147") (name "unconnected-(JP8-Pad2)") (class "Default")
      (node (ref "JP8") (pin "2") (pinfunction "2_2") (pintype "passive"))
    )
    (net (code "148") (name "unconnected-(JP8-Pad7)") (class "Default")
      (node (ref "JP8") (pin "7") (pinfunction "7_7") (pintype "passive"))
    )
    (net (code "149") (name "unconnected-(JP8-Pad8)") (class "Default")
      (node (ref "JP8") (pin "8") (pinfunction "8_8") (pintype "passive"))
    )
    (net (code "150") (name "unconnected-(JP8-Pad9)") (class "Default")
      (node (ref "JP8") (pin "9") (pinfunction "9_9") (pintype "passive"))
    )
    (net (code "151") (name "unconnected-(JP8-Pad10)") (class "Default")
      (node (ref "JP8") (pin "10") (pinfunction "10_10") (pintype "passive"))
    )
    (net (code "152") (name "unconnected-(JP8-Pad11)") (class "Default")
      (node (ref "JP8") (pin "11") (pinfunction "11_11") (pintype "passive"))
    )
    (net (code "153") (name "unconnected-(JP8-Pad12)") (class "Default")
      (node (ref "JP8") (pin "12") (pinfunction "12_12") (pintype "passive"))
    )
    (net (code "154") (name "unconnected-(JP8-Pad13)") (class "Default")
      (node (ref "JP8") (pin "13") (pinfunction "13_13") (pintype "passive"))
    )
    (net (code "155") (name "unconnected-(JP8-Pad14)") (class "Default")
      (node (ref "JP8") (pin "14") (pinfunction "14_14") (pintype "passive"))
    )
    (net (code "156") (name "unconnected-(JP8-Pad15)") (class "Default")
      (node (ref "JP8") (pin "15") (pinfunction "15_15") (pintype "passive"))
    )
    (net (code "157") (name "unconnected-(JP8-Pad16)") (class "Default")
      (node (ref "JP8") (pin "16") (pinfunction "16_16") (pintype "passive"))
    )
    (net (code "158") (name "unconnected-(JP8-Pad17)") (class "Default")
      (node (ref "JP8") (pin "17") (pinfunction "17_17") (pintype "passive"))
    )
    (net (code "159") (name "unconnected-(JP8-Pad18)") (class "Default")
      (node (ref "JP8") (pin "18") (pinfunction "18_18") (pintype "passive"))
    )
    (net (code "160") (name "unconnected-(JP9-Pad1)") (class "Default")
      (node (ref "JP9") (pin "1") (pinfunction "1_1") (pintype "passive"))
    )
    (net (code "161") (name "unconnected-(JP9-Pad2)") (class "Default")
      (node (ref "JP9") (pin "2") (pinfunction "2_2") (pintype "passive"))
    )
    (net (code "162") (name "unconnected-(JP9-Pad3)") (class "Default")
      (node (ref "JP9") (pin "3") (pinfunction "3_3") (pintype "passive"))
    )
    (net (code "163") (name "unconnected-(JP9-Pad4)") (class "Default")
      (node (ref "JP9") (pin "4") (pinfunction "4_4") (pintype "passive"))
    )
    (net (code "164") (name "unconnected-(JP9-Pad5)") (class "Default")
      (node (ref "JP9") (pin "5") (pinfunction "5_5") (pintype "passive"))
    )
    (net (code "165") (name "unconnected-(JP9-Pad6)") (class "Default")
      (node (ref "JP9") (pin "6") (pinfunction "6_6") (pintype "passive"))
    )
    (net (code "166") (name "unconnected-(JP9-Pad11)") (class "Default")
      (node (ref "JP9") (pin "11") (pinfunction "11_11") (pintype "passive"))
    )
    (net (code "167") (name "unconnected-(JP9-Pad21)") (class "Default")
      (node (ref "JP9") (pin "21") (pinfunction "21_21") (pintype "passive"))
    )
    (net (code "168") (name "unconnected-(JP9-Pad23)") (class "Default")
      (node (ref "JP9") (pin "23") (pinfunction "23_23") (pintype "passive"))
    )
    (net (code "169") (name "unconnected-(JP9-Pad25)") (class "Default")
      (node (ref "JP9") (pin "25") (pinfunction "25_25") (pintype "passive"))
    )
    (net (code "170") (name "unconnected-(JP9-Pad26)") (class "Default")
      (node (ref "JP9") (pin "26") (pinfunction "26_26") (pintype "passive"))
    )
    (net (code "171") (name "unconnected-(JP9-Pad27)") (class "Default")
      (node (ref "JP9") (pin "27") (pinfunction "27_27") (pintype "passive"))
    )
    (net (code "172") (name "unconnected-(JP9-Pad28)") (class "Default")
      (node (ref "JP9") (pin "28") (pinfunction "28_28") (pintype "passive"))
    )
    (net (code "173") (name "unconnected-(JP9-Pad29)") (class "Default")
      (node (ref "JP9") (pin "29") (pinfunction "29_29") (pintype "passive"))
    )
    (net (code "174") (name "unconnected-(JP9-Pad30)") (class "Default")
      (node (ref "JP9") (pin "30") (pinfunction "30_30") (pintype "passive"))
    )
    (net (code "175") (name "unconnected-(JP10-Pad1)") (class "Default")
      (node (ref "JP10") (pin "1") (pinfunction "1_1") (pintype "passive"))
    )
    (net (code "176") (name "unconnected-(JP10-Pad2)") (class "Default")
      (node (ref "JP10") (pin "2") (pinfunction "2_2") (pintype "passive"))
    )
    (net (code "177") (name "unconnected-(JP10-Pad3)") (class "Default")
      (node (ref "JP10") (pin "3") (pinfunction "3_3") (pintype "passive"))
    )
    (net (code "178") (name "unconnected-(JP10-Pad4)") (class "Default")
      (node (ref "JP10") (pin "4") (pinfunction "4_4") (pintype "passive"))
    )
    (net (code "179") (name "unconnected-(JP10-Pad5)") (class "Default")
      (node (ref "JP10") (pin "5") (pinfunction "5_5") (pintype "passive"))
    )
    (net (code "180") (name "unconnected-(JP10-Pad6)") (class "Default")
      (node (ref "JP10") (pin "6") (pinfunction "6_6") (pintype "passive"))
    )
    (net (code "181") (name "unconnected-(JP10-Pad11)") (class "Default")
      (node (ref "JP10") (pin "11") (pinfunction "11_11") (pintype "passive"))
    )
    (net (code "182") (name "unconnected-(JP10-Pad21)") (class "Default")
      (node (ref "JP10") (pin "21") (pinfunction "21_21") (pintype "passive"))
    )
    (net (code "183") (name "unconnected-(JP10-Pad22)") (class "Default")
      (node (ref "JP10") (pin "22") (pinfunction "22_22") (pintype "passive"))
    )
    (net (code "184") (name "unconnected-(JP10-Pad23)") (class "Default")
      (node (ref "JP10") (pin "23") (pinfunction "23_23") (pintype "passive"))
    )
    (net (code "185") (name "unconnected-(JP10-Pad25)") (class "Default")
      (node (ref "JP10") (pin "25") (pinfunction "25_25") (pintype "passive"))
    )
    (net (code "186") (name "unconnected-(JP10-Pad26)") (class "Default")
      (node (ref "JP10") (pin "26") (pinfunction "26_26") (pintype "passive"))
    )
    (net (code "187") (name "unconnected-(JP10-Pad27)") (class "Default")
      (node (ref "JP10") (pin "27") (pinfunction "27_27") (pintype "passive"))
    )
    (net (code "188") (name "unconnected-(JP10-Pad28)") (class "Default")
      (node (ref "JP10") (pin "28") (pinfunction "28_28") (pintype "passive"))
    )
    (net (code "189") (name "unconnected-(JP10-Pad29)") (class "Default")
      (node (ref "JP10") (pin "29") (pinfunction "29_29") (pintype "passive"))
    )
    (net (code "190") (name "unconnected-(JP10-Pad30)") (class "Default")
      (node (ref "JP10") (pin "30") (pinfunction "30_30") (pintype "passive"))
    )
    (net (code "191") (name "unconnected-(JP11-Pad1)") (class "Default")
      (node (ref "JP11") (pin "1") (pinfunction "1_1") (pintype "passive"))
    )
    (net (code "192") (name "unconnected-(JP11-Pad2)") (class "Default")
      (node (ref "JP11") (pin "2") (pinfunction "2_2") (pintype "passive"))
    )
    (net (code "193") (name "unconnected-(JP11-Pad3)") (class "Default")
      (node (ref "JP11") (pin "3") (pinfunction "3_3") (pintype "passive"))
    )
    (net (code "194") (name "unconnected-(JP11-Pad4)") (class "Default")
      (node (ref "JP11") (pin "4") (pinfunction "4_4") (pintype "passive"))
    )
    (net (code "195") (name "unconnected-(JP11-Pad5)") (class "Default")
      (node (ref "JP11") (pin "5") (pinfunction "5_5") (pintype "passive"))
    )
    (net (code "196") (name "unconnected-(JP11-Pad6)") (class "Default")
      (node (ref "JP11") (pin "6") (pinfunction "6_6") (pintype "passive"))
    )
    (net (code "197") (name "unconnected-(JP11-Pad11)") (class "Default")
      (node (ref "JP11") (pin "11") (pinfunction "11_11") (pintype "passive"))
    )
    (net (code "198") (name "unconnected-(JP11-Pad21)") (class "Default")
      (node (ref "JP11") (pin "21") (pinfunction "21_21") (pintype "passive"))
    )
    (net (code "199") (name "unconnected-(JP11-Pad23)") (class "Default")
      (node (ref "JP11") (pin "23") (pinfunction "23_23") (pintype "passive"))
    )
    (net (code "200") (name "unconnected-(JP11-Pad24)") (class "Default")
      (node (ref "JP11") (pin "24") (pinfunction "24_24") (pintype "passive"))
    )
    (net (code "201") (name "unconnected-(JP11-Pad25)") (class "Default")
      (node (ref "JP11") (pin "25") (pinfunction "25_25") (pintype "passive"))
    )
    (net (code "202") (name "unconnected-(JP11-Pad26)") (class "Default")
      (node (ref "JP11") (pin "26") (pinfunction "26_26") (pintype "passive"))
    )
    (net (code "203") (name "unconnected-(JP11-Pad27)") (class "Default")
      (node (ref "JP11") (pin "27") (pinfunction "27_27") (pintype "passive"))
    )
    (net (code "204") (name "unconnected-(JP11-Pad28)") (class "Default")
      (node (ref "JP11") (pin "28") (pinfunction "28_28") (pintype "passive"))
    )
    (net (code "205") (name "unconnected-(JP11-Pad29)") (class "Default")
      (node (ref "JP11") (pin "29") (pinfunction "29_29") (pintype "passive"))
    )
    (net (code "206") (name "unconnected-(JP11-Pad30)") (class "Default")
      (node (ref "JP11") (pin "30") (pinfunction "30_30") (pintype "passive"))
    )
    (net (code "207") (name "unconnected-(MONO_OUT-PadRING)") (class "Default")
      (node (ref "MONO_OUT") (pin "RING") (pinfunction "RING_RING") (pintype "bidirectional"))
    )
    (net (code "208") (name "unconnected-(MONO_OUT-PadRSH)") (class "Default")
      (node (ref "MONO_OUT") (pin "RSH") (pinfunction "RSH_RSH") (pintype "bidirectional"))
    )
    (net (code "209") (name "unconnected-(MONO_OUT-PadTSH)") (class "Default")
      (node (ref "MONO_OUT") (pin "TSH") (pinfunction "TSH_TSH") (pintype "bidirectional"))
    )
    (net (code "210") (name "unconnected-(STEREO_OUT-PadRSH)") (class "Default")
      (node (ref "STEREO_OUT") (pin "RSH") (pinfunction "RSH_RSH") (pintype "bidirectional"))
    )
    (net (code "211") (name "unconnected-(STEREO_OUT-PadTSH)") (class "Default")
      (node (ref "STEREO_OUT") (pin "TSH") (pinfunction "TSH_TSH") (pintype "bidirectional"))
    )
    (net (code "212") (name "unconnected-(U1-NC-Pad4)") (class "Default")
      (node (ref "U1") (pin "4") (pinfunction "NC_4") (pintype "no_connect"))
    )
    (net (code "213") (name "unconnected-(U1-NC_2-Pad2)") (class "Default")
      (node (ref "U1") (pin "2") (pinfunction "NC_2_2") (pintype "no_connect"))
    )
    (net (code "214") (name "unconnected-(U1-NC_3-Pad3)") (class "Default")
      (node (ref "U1") (pin "3") (pinfunction "NC_3_3") (pintype "no_connect"))
    )
    (net (code "215") (name "unconnected-(U1-REF-Pad1)") (class "Default")
      (node (ref "U1") (pin "1") (pinfunction "REF_1") (pintype "bidirectional"))
    )
  )
)
